# ProPrj_LXBRC-STM32F405__2024-08-19.net
KiCad netlist of a schematic drawn in EasyEDA Pro
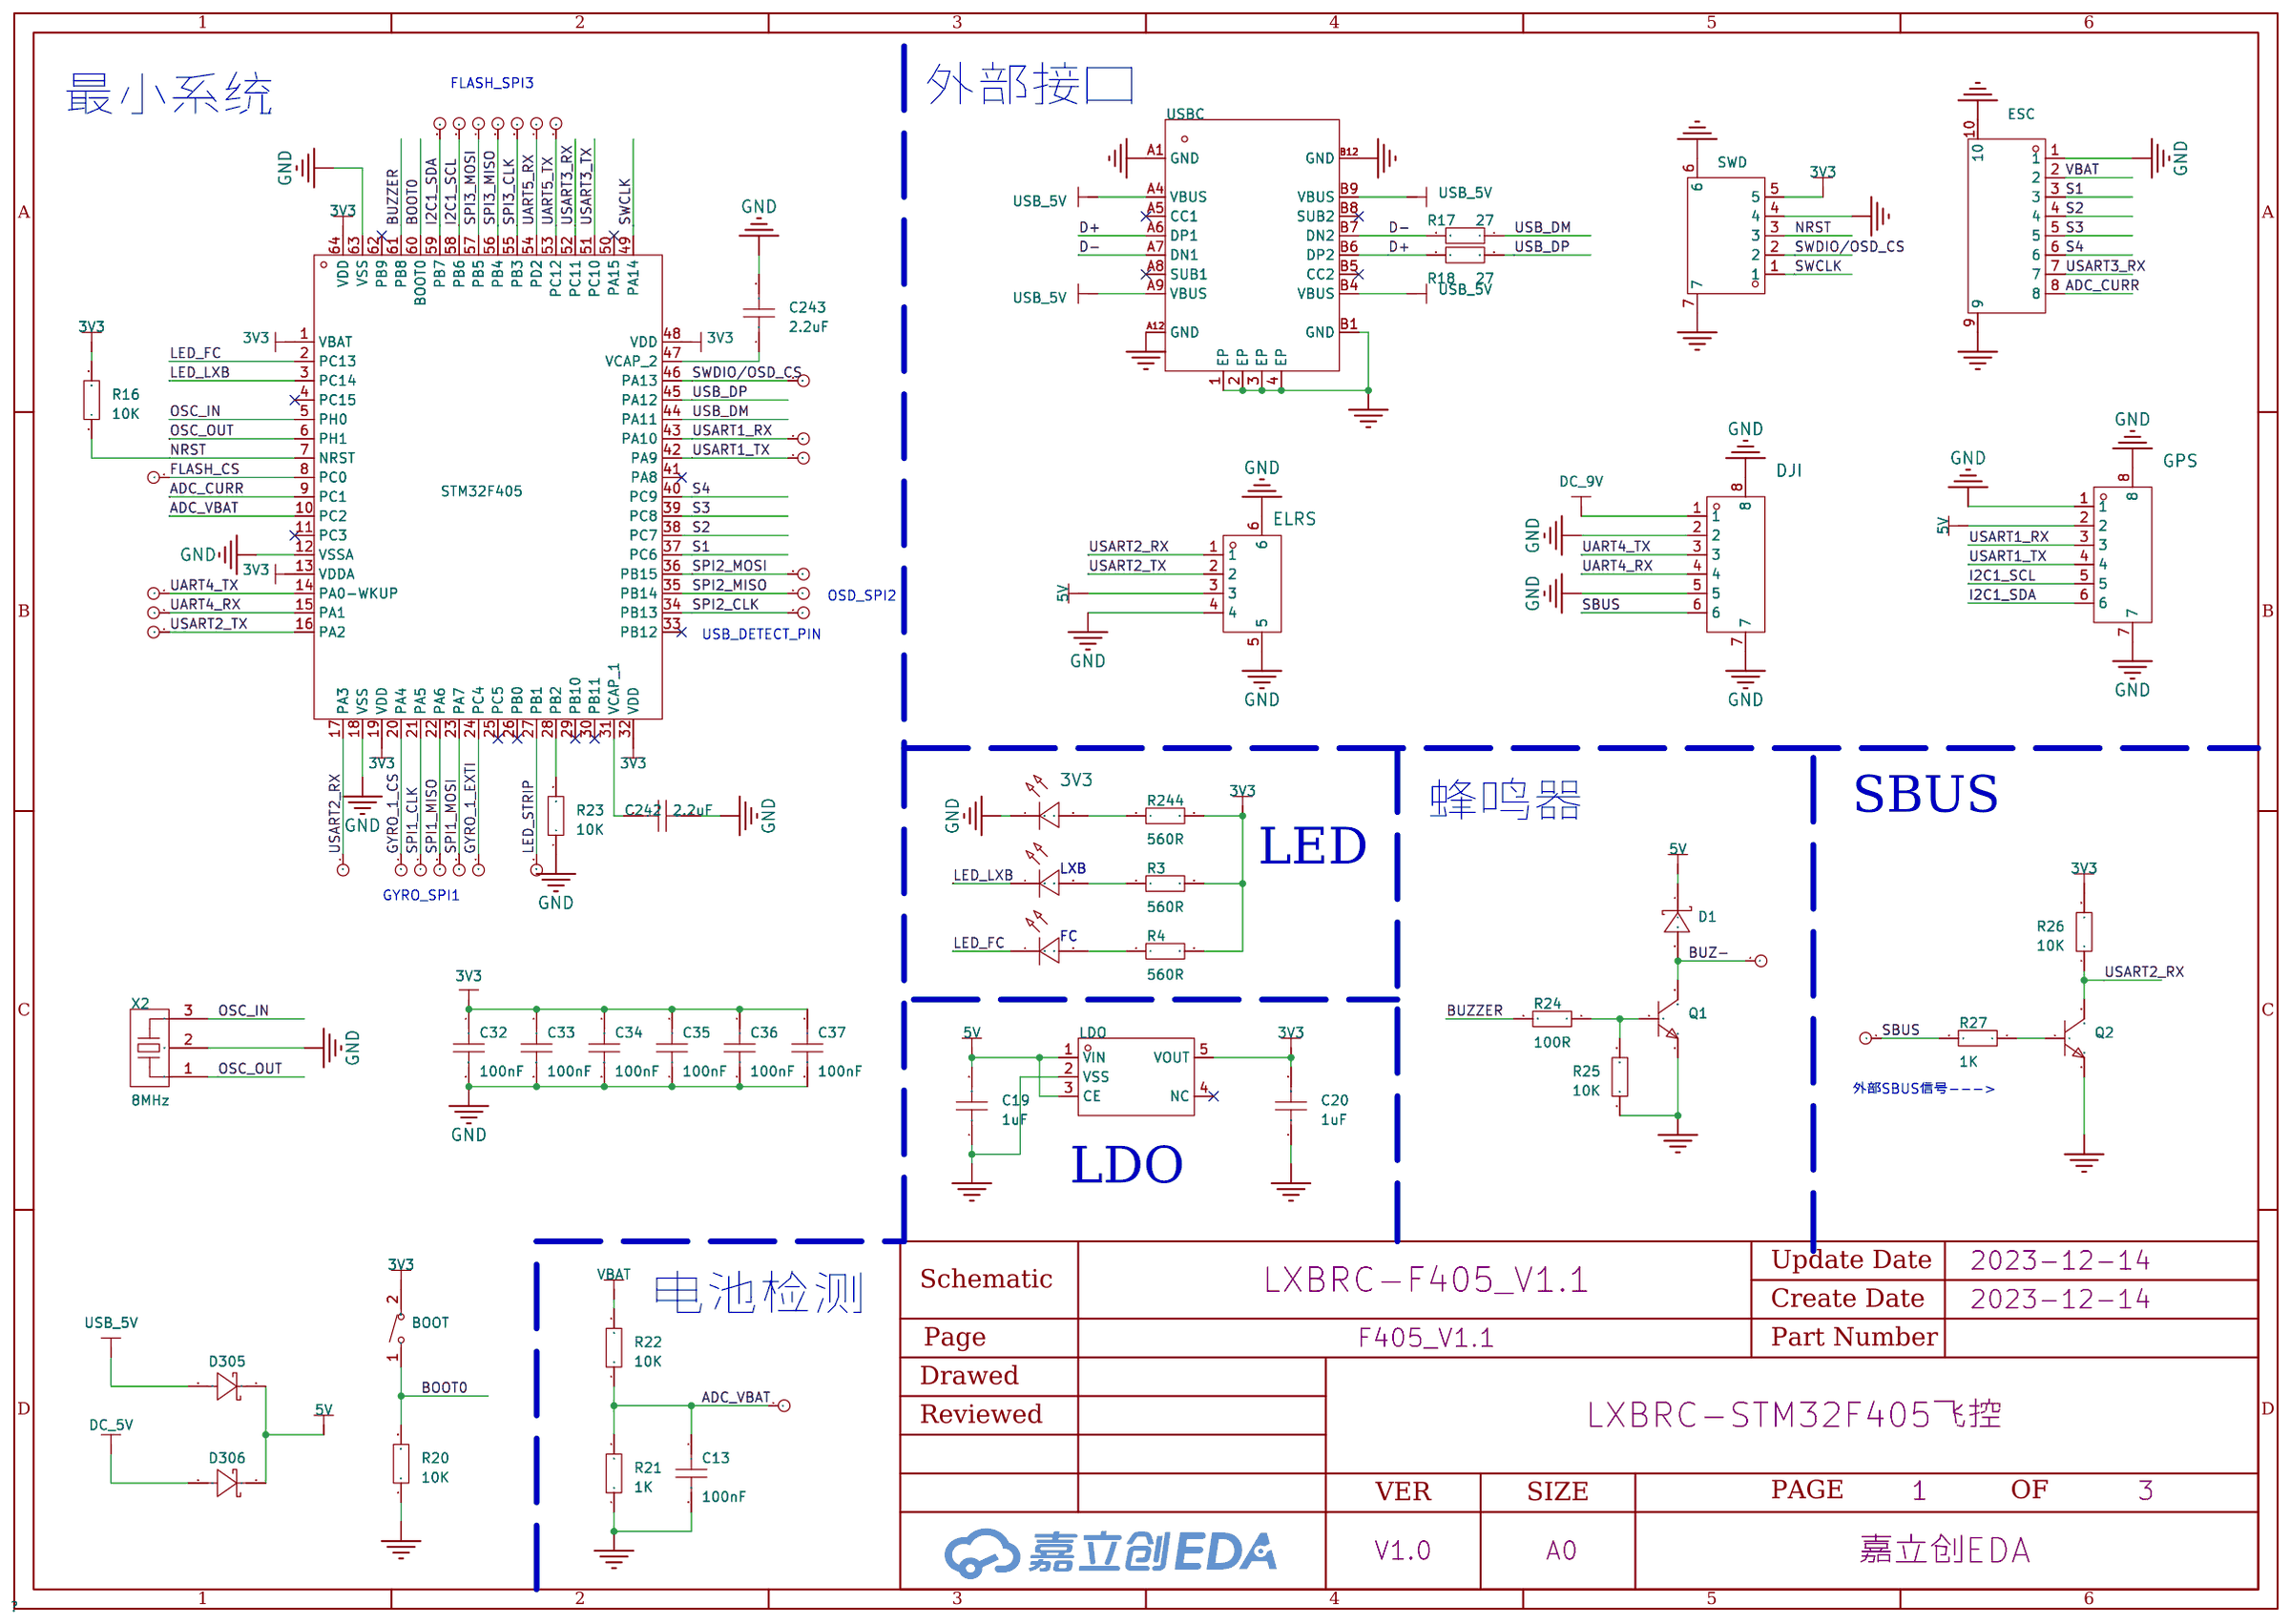
[diagram p0: F405_V1.1]
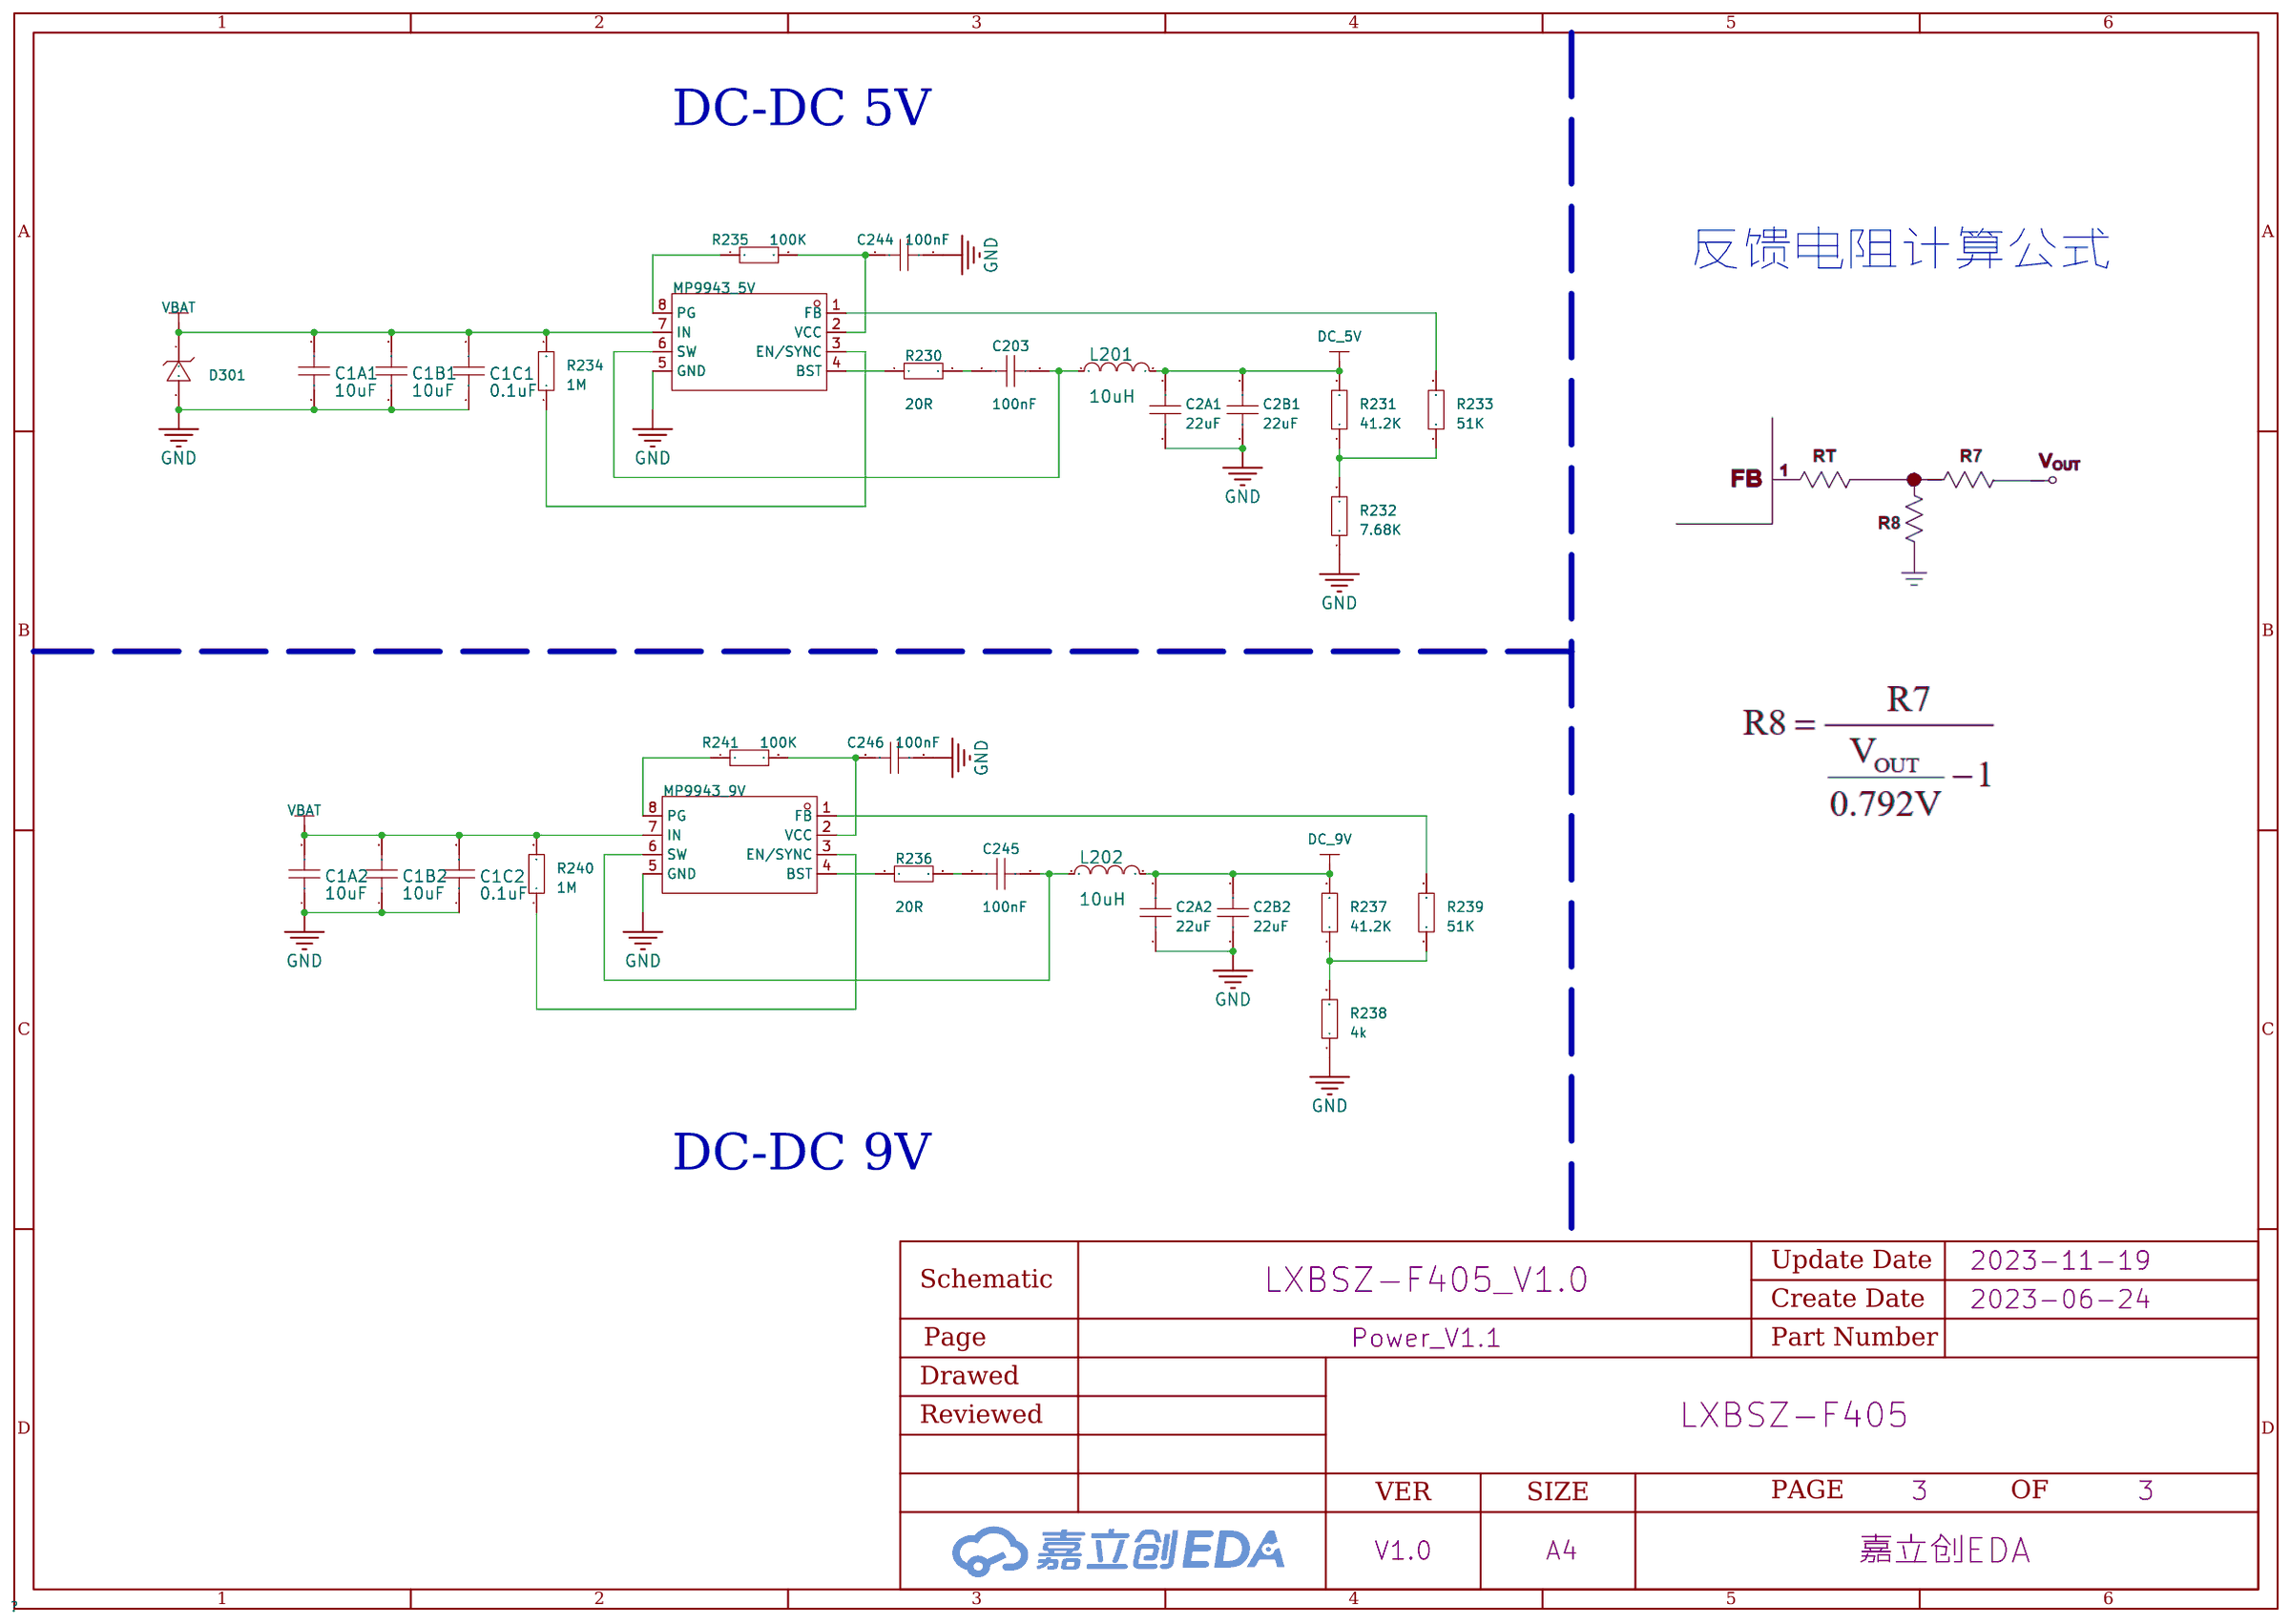
[diagram p1: Power_V1.1]
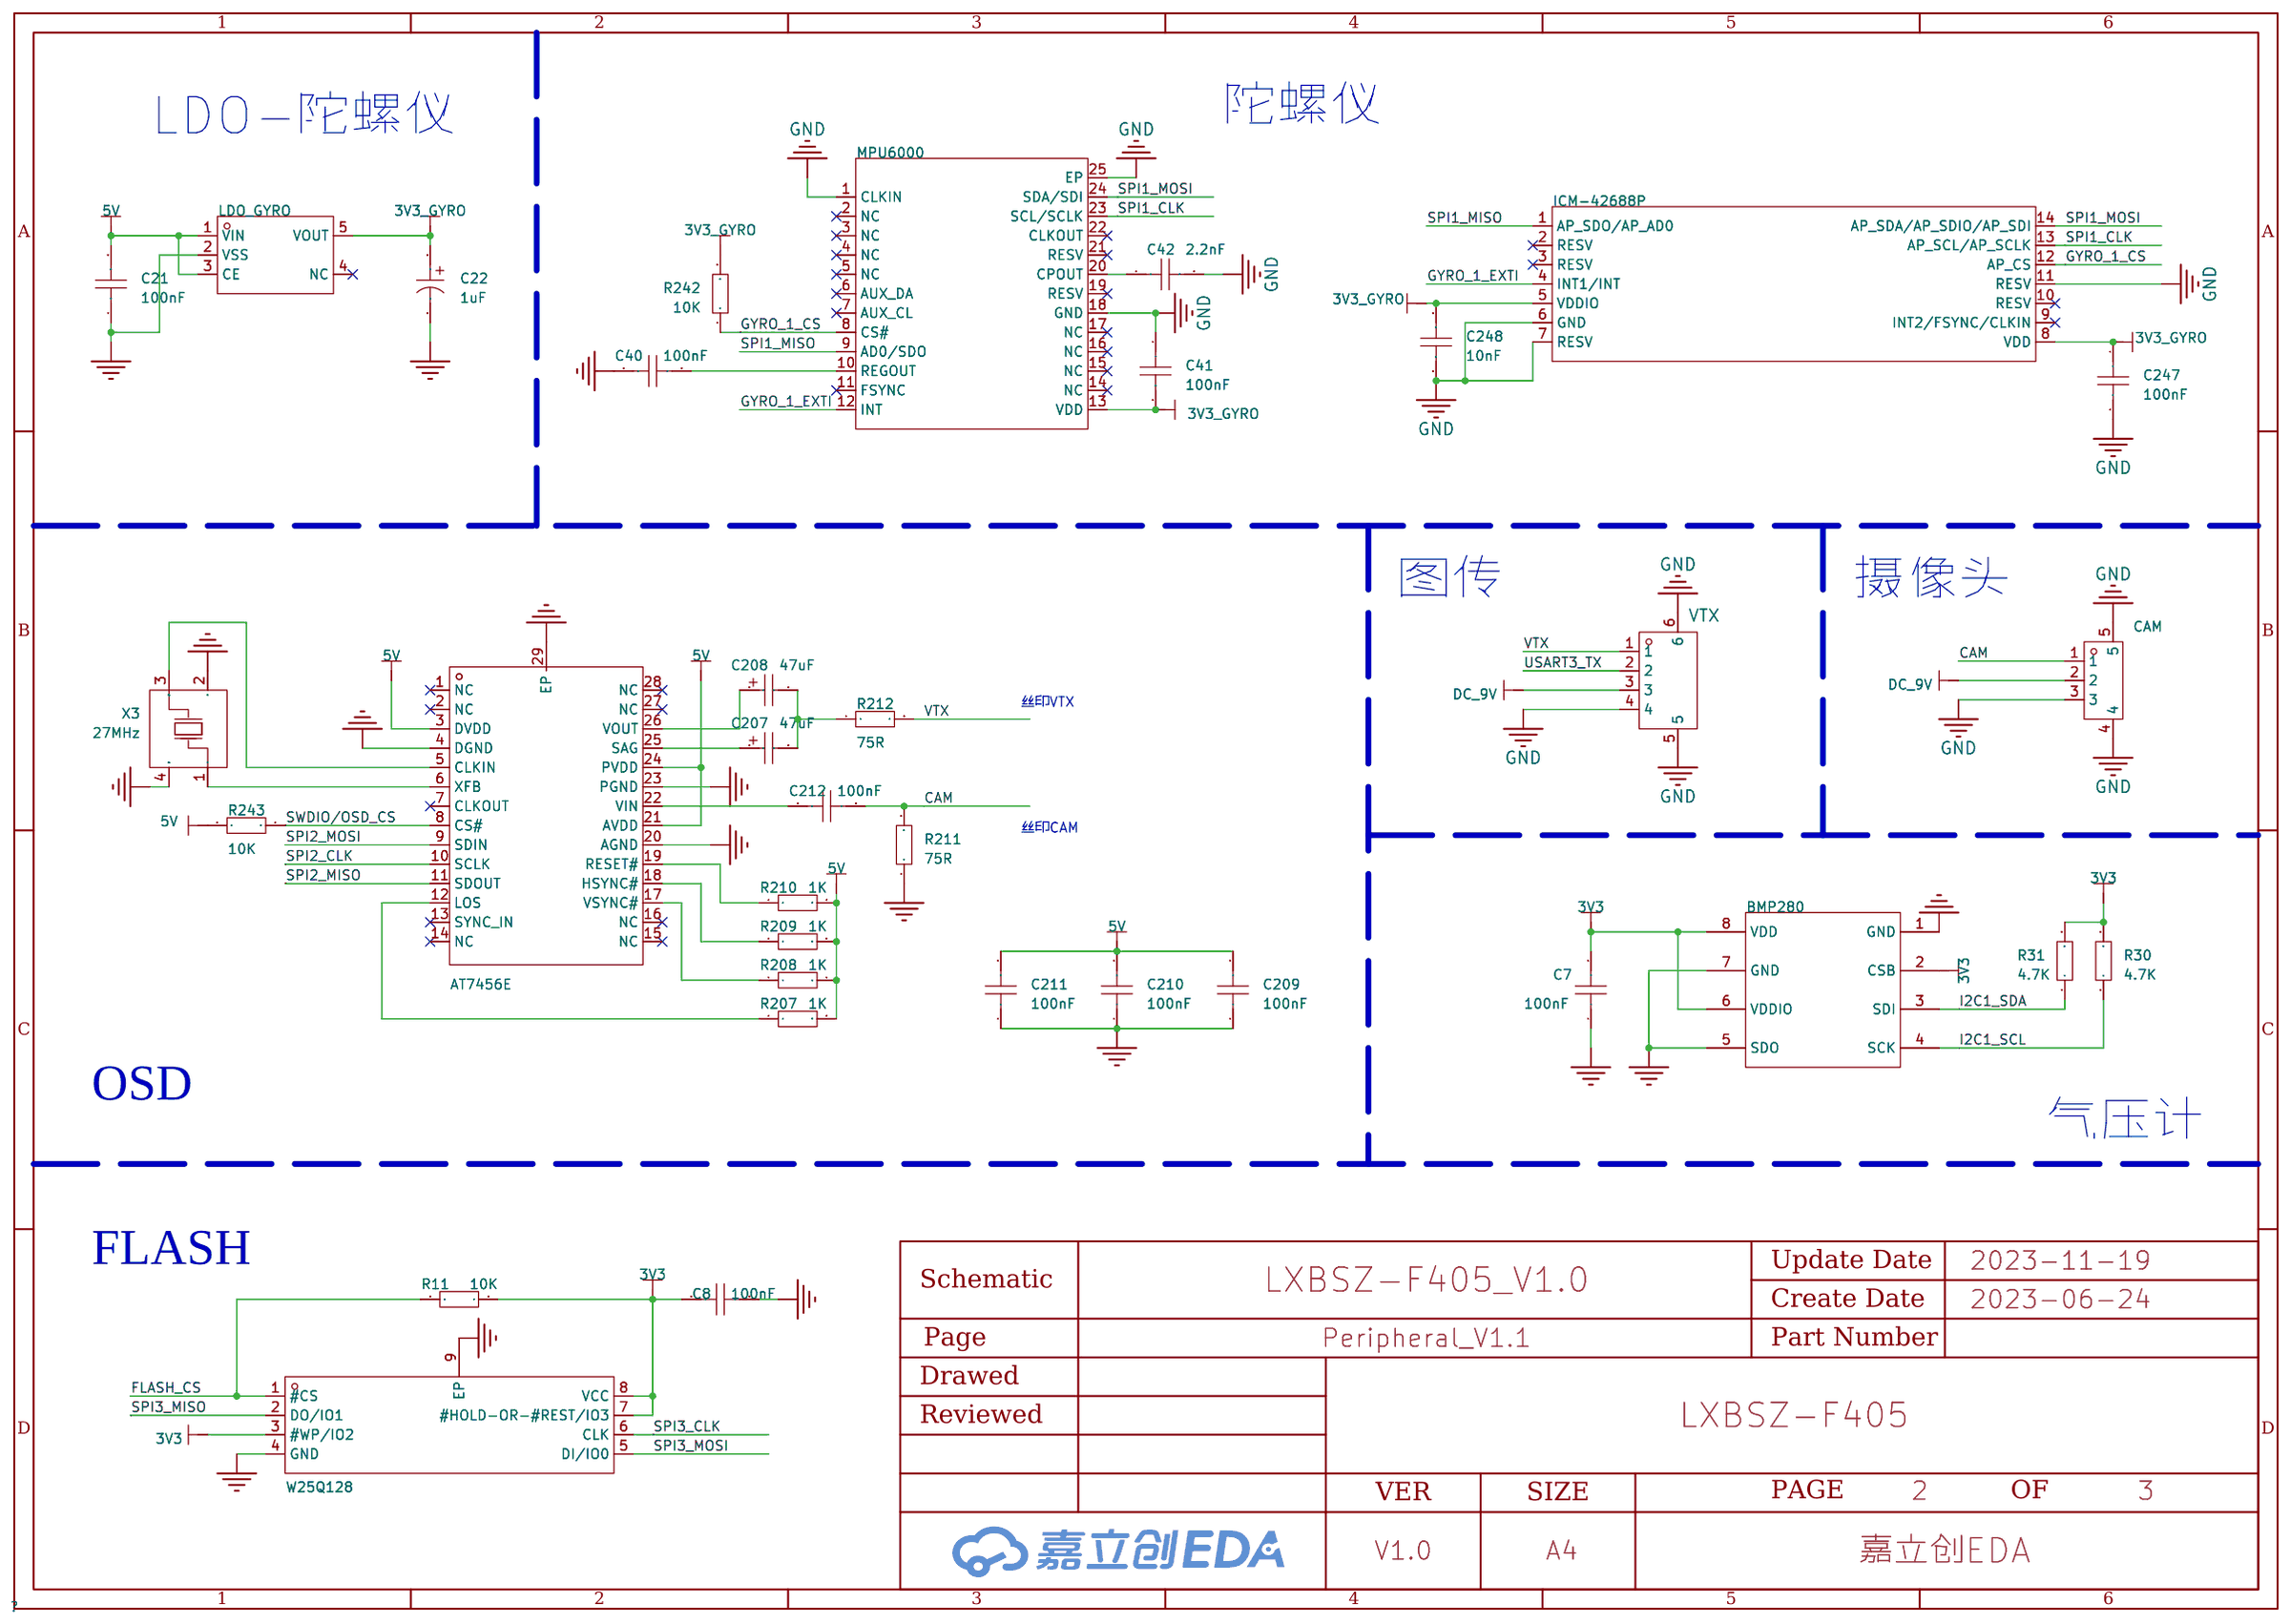
[diagram p2: Peripheral_V1.1]

(export (version "E")
  (design (tool "Eeschema 10.0.6"))
  (components
    (comp (ref "3V3")
      (value "~")
      (footprint "easyedapro:LED_0402")
      (libsource (lib "easyedapro") (part "LED_R"))
    )
    (comp (ref "BOOT")
      (value "TS2306A 200gf 002")
      (footprint "easyedapro:SW-SMD_L3.0-W2.0-LS3.5")
      (fields (field (name "Manufacturer") "SHOU HAN(首韩)"))
      (libsource (lib "easyedapro") (part "TS2306A 200GF 002"))
    )
    (comp (ref "C13")
      (value "100nF")
      (footprint "easyedapro:C0402")
      (libsource (lib "easyedapro") (part "CapAcitance"))
    )
    (comp (ref "C19")
      (value "1uF")
      (footprint "easyedapro:C0402")
      (libsource (lib "easyedapro") (part "CapAcitance"))
    )
    (comp (ref "C20")
      (value "1uF")
      (footprint "easyedapro:C0402")
      (libsource (lib "easyedapro") (part "CapAcitance"))
    )
    (comp (ref "C32")
      (value "100nF")
      (footprint "easyedapro:C0402")
      (libsource (lib "easyedapro") (part "CapAcitance"))
    )
    (comp (ref "C33")
      (value "100nF")
      (footprint "easyedapro:C0402")
      (libsource (lib "easyedapro") (part "CapAcitance"))
    )
    (comp (ref "C34")
      (value "100nF")
      (footprint "easyedapro:C0402")
      (libsource (lib "easyedapro") (part "CapAcitance"))
    )
    (comp (ref "C35")
      (value "100nF")
      (footprint "easyedapro:C0402")
      (libsource (lib "easyedapro") (part "CapAcitance"))
    )
    (comp (ref "C36")
      (value "100nF")
      (footprint "easyedapro:C0402")
      (libsource (lib "easyedapro") (part "CapAcitance"))
    )
    (comp (ref "C37")
      (value "100nF")
      (footprint "easyedapro:C0402")
      (libsource (lib "easyedapro") (part "CapAcitance"))
    )
    (comp (ref "C242")
      (value "2.2uF")
      (footprint "easyedapro:C0402")
      (libsource (lib "easyedapro") (part "CapAcitance"))
    )
    (comp (ref "C243")
      (value "2.2uF")
      (footprint "easyedapro:C0402")
      (libsource (lib "easyedapro") (part "CapAcitance"))
    )
    (comp (ref "D1")
      (value "B5819WS")
      (footprint "easyedapro:SOD-323_L1.8-W1.3-LS2.5-RD")
      (description "直流反向耐压(Vr):40V;平均整流电流(Io):1A;正向压降(Vf):900mV@3A;")
      (fields (field (name "Manufacturer") "Slkor(萨科微)"))
      (libsource (lib "easyedapro") (part "B5819WS_C488405"))
    )
    (comp (ref "D305")
      (value "B5819W")
      (footprint "easyedapro:SOD-123F_L2.7-W1.6-LS3.8-RD-1")
      (description "二极管配置:-;直流反向耐压(Vr):40V;平均整流电流(Io):1A;正向压降(Vf):580mV@1A;")
      (fields (field (name "Manufacturer") "GOODWORK(固得沃克)"))
      (libsource (lib "easyedapro") (part "B5819W_C2943878"))
    )
    (comp (ref "D306")
      (value "B5819W")
      (footprint "easyedapro:SOD-123F_L2.7-W1.6-LS3.8-RD-1")
      (description "二极管配置:-;直流反向耐压(Vr):40V;平均整流电流(Io):1A;正向压降(Vf):580mV@1A;")
      (fields (field (name "Manufacturer") "GOODWORK(固得沃克)"))
      (libsource (lib "easyedapro") (part "B5819W_C2943878"))
    )
    (comp (ref "DJI")
      (value "ZX-SH1.0-6PWT")
      (footprint "easyedapro:CONN-SMD_6P-P1.00_MEGASTAR_ZX-SH1.0-6PWT")
      (fields (field (name "Manufacturer") "Megastar(兆星)"))
      (libsource (lib "easyedapro") (part "ZX-SH1.0-6PWT"))
    )
    (comp (ref "ELRS")
      (value "ZX-SH1.0-4PWT")
      (footprint "easyedapro:CONN-SMD_4P-P1.00_MEGASTAR_ZX-SH1.0-4PWT")
      (fields (field (name "Manufacturer") "Megastar(兆星)"))
      (libsource (lib "easyedapro") (part "ZX-SH1.0-4PWT"))
    )
    (comp (ref "ESC")
      (value "A1002WR-S-8P")
      (footprint "easyedapro:CONN-SMD_A1002WR-S-8P")
      (description "系列:SH;连接器类型:接头;触头类型:公形引脚;间距:0.039quot;(1.00mm);针脚数:8;")
      (fields (field (name "Manufacturer") "CJT(长江连接器)"))
      (libsource (lib "easyedapro") (part "A1002WR-S-8P"))
    )
    (comp (ref "FC")
      (value "~")
      (footprint "easyedapro:LED_0402")
      (libsource (lib "easyedapro") (part "LED_B"))
    )
    (comp (ref "G2") (value "~") (footprint "easyedapro:通孔焊盘") (libsource (lib "easyedapro") (part "焊盘")))
    (comp (ref "G3") (value "~") (footprint "easyedapro:通孔焊盘") (libsource (lib "easyedapro") (part "焊盘")))
    (comp (ref "G4") (value "~") (footprint "easyedapro:通孔焊盘") (libsource (lib "easyedapro") (part "焊盘")))
    (comp (ref "G7") (value "~") (footprint "easyedapro:通孔焊盘") (libsource (lib "easyedapro") (part "焊盘")))
    (comp (ref "G8") (value "~") (footprint "easyedapro:通孔焊盘") (libsource (lib "easyedapro") (part "焊盘")))
    (comp (ref "G9") (value "~") (footprint "easyedapro:通孔焊盘") (libsource (lib "easyedapro") (part "焊盘")))
    (comp (ref "G10") (value "~") (footprint "easyedapro:通孔焊盘") (libsource (lib "easyedapro") (part "焊盘")))
    (comp (ref "G11") (value "~") (footprint "easyedapro:通孔焊盘") (libsource (lib "easyedapro") (part "焊盘")))
    (comp (ref "G12") (value "~") (footprint "easyedapro:通孔焊盘") (libsource (lib "easyedapro") (part "焊盘")))
    (comp (ref "G13") (value "~") (footprint "easyedapro:通孔焊盘") (libsource (lib "easyedapro") (part "焊盘")))
    (comp (ref "G14") (value "~") (footprint "easyedapro:通孔焊盘") (libsource (lib "easyedapro") (part "焊盘")))
    (comp (ref "G15") (value "~") (footprint "easyedapro:通孔焊盘") (libsource (lib "easyedapro") (part "焊盘")))
    (comp (ref "G16") (value "~") (footprint "easyedapro:通孔焊盘") (libsource (lib "easyedapro") (part "焊盘")))
    (comp (ref "G17") (value "~") (footprint "easyedapro:通孔焊盘") (libsource (lib "easyedapro") (part "焊盘")))
    (comp (ref "G18") (value "~") (footprint "easyedapro:通孔焊盘") (libsource (lib "easyedapro") (part "焊盘")))
    (comp (ref "G19") (value "~") (footprint "easyedapro:通孔焊盘") (libsource (lib "easyedapro") (part "焊盘")))
    (comp (ref "G20") (value "~") (footprint "easyedapro:通孔焊盘") (libsource (lib "easyedapro") (part "焊盘")))
    (comp (ref "G21") (value "~") (footprint "easyedapro:通孔焊盘") (libsource (lib "easyedapro") (part "焊盘")))
    (comp (ref "G22") (value "~") (footprint "easyedapro:通孔焊盘") (libsource (lib "easyedapro") (part "焊盘")))
    (comp (ref "G23") (value "~") (footprint "easyedapro:通孔焊盘") (libsource (lib "easyedapro") (part "焊盘")))
    (comp (ref "G24") (value "~") (footprint "easyedapro:通孔焊盘") (libsource (lib "easyedapro") (part "焊盘")))
    (comp (ref "G25") (value "~") (footprint "easyedapro:通孔焊盘") (libsource (lib "easyedapro") (part "焊盘")))
    (comp (ref "G26") (value "~") (footprint "easyedapro:通孔焊盘") (libsource (lib "easyedapro") (part "焊盘")))
    (comp (ref "G27") (value "~") (footprint "easyedapro:通孔焊盘") (libsource (lib "easyedapro") (part "焊盘")))
    (comp (ref "G28") (value "~") (footprint "easyedapro:通孔焊盘") (libsource (lib "easyedapro") (part "焊盘")))
    (comp (ref "GPS")
      (value "ZX-SH1.0-6PWT")
      (footprint "easyedapro:CONN-SMD_6P-P1.00_MEGASTAR_ZX-SH1.0-6PWT")
      (fields (field (name "Manufacturer") "Megastar(兆星)"))
      (libsource (lib "easyedapro") (part "ZX-SH1.0-6PWT"))
    )
    (comp (ref "HP15") (value "~") (footprint "easyedapro:通孔焊盘") (libsource (lib "easyedapro") (part "焊盘")))
    (comp (ref "LDO")
      (value "CJ6206B33M")
      (footprint "easyedapro:SOT-23-5_L2.9-W1.6-P0.95-LS2.8-BL")
      (fields (field (name "Manufacturer") "CJ(江苏长电/长晶)"))
      (libsource (lib "easyedapro") (part "CJ6206B33M"))
    )
    (comp (ref "LXB")
      (value "~")
      (footprint "easyedapro:LED_0402")
      (libsource (lib "easyedapro") (part "LED_G"))
    )
    (comp (ref "Q1")
      (value "~")
      (footprint "easyedapro:S8050_SOT-23")
      (libsource (lib "easyedapro") (part "NPN"))
    )
    (comp (ref "Q2")
      (value "~")
      (footprint "easyedapro:S8050_SOT-23")
      (libsource (lib "easyedapro") (part "NPN"))
    )
    (comp (ref "R3") (value "560R") (footprint "easyedapro:R0402") (libsource (lib "easyedapro") (part "电阻")))
    (comp (ref "R4") (value "560R") (footprint "easyedapro:R0402") (libsource (lib "easyedapro") (part "电阻")))
    (comp (ref "R16") (value "10K") (footprint "easyedapro:R0402") (libsource (lib "easyedapro") (part "电阻")))
    (comp (ref "R17") (value "27") (footprint "easyedapro:R0402") (libsource (lib "easyedapro") (part "电阻")))
    (comp (ref "R18") (value "27") (footprint "easyedapro:R0402") (libsource (lib "easyedapro") (part "电阻")))
    (comp (ref "R20") (value "10K") (footprint "easyedapro:R0402") (libsource (lib "easyedapro") (part "电阻")))
    (comp (ref "R21") (value "1K") (footprint "easyedapro:R0402") (libsource (lib "easyedapro") (part "电阻")))
    (comp (ref "R22") (value "10K") (footprint "easyedapro:R0402") (libsource (lib "easyedapro") (part "电阻")))
    (comp (ref "R23") (value "10K") (footprint "easyedapro:R0402") (libsource (lib "easyedapro") (part "电阻")))
    (comp (ref "R24")
      (value "100R")
      (footprint "easyedapro:R0402")
      (libsource (lib "easyedapro") (part "电阻"))
    )
    (comp (ref "R25") (value "10K") (footprint "easyedapro:R0402") (libsource (lib "easyedapro") (part "电阻")))
    (comp (ref "R26") (value "10K") (footprint "easyedapro:R0402") (libsource (lib "easyedapro") (part "电阻")))
    (comp (ref "R27") (value "1K") (footprint "easyedapro:R0402") (libsource (lib "easyedapro") (part "电阻")))
    (comp (ref "R244")
      (value "560R")
      (footprint "easyedapro:R0402")
      (libsource (lib "easyedapro") (part "电阻"))
    )
    (comp (ref "RC1") (value "~") (footprint "easyedapro:通孔焊盘") (libsource (lib "easyedapro") (part "焊盘")))
    (comp (ref "STM32F405")
      (value "STM32F405RGT6V")
      (footprint "easyedapro:LQFP-64_L10.0-W10.0-P0.50-LS12.0-BL")
      (fields (field (name "Manufacturer") "ST(意法半导体)"))
      (libsource (lib "easyedapro") (part "STM32F405RGT6V"))
    )
    (comp (ref "SWD")
      (value "A1002WR-S-5P")
      (footprint "easyedapro:CONN-SMD_A1002WR-S-5P")
      (description "系列:SH;连接器类型:接头;触头类型:公形引脚;间距:0.039quot;(1.00mm);针脚数:5;")
      (fields (field (name "Manufacturer") "CJT(长江连接器)"))
      (libsource (lib "easyedapro") (part "A1002WR-S-5P"))
    )
    (comp (ref "USBC")
      (value "KH-TYPE-C-16P")
      (footprint "easyedapro:USB-C-SMD_KH-TYPE-C-16P")
      (description "连接器类型:Type-C;标准:-;公母:母座;触点数量:16;端口数量:1;安装方式:卧贴;额定电流 - 电源:3A;工作温度范围:-40°C~+85°C;")
      (fields (field (name "Manufacturer") "kinghelm(金航标)"))
      (libsource (lib "easyedapro") (part "KH-TYPE-C-16P"))
    )
    (comp (ref "X2")
      (value "8MHz")
      (footprint "easyedapro:OSC-SMD_3P-L3.2-W1.3-P1.2-L")
      (description "频率:8MHz;频率容差:±0.1%;内置负载电容:33pF;谐振阻抗:40Ω;")
      (fields
        (field (name "Manufacturer Part") "CSTCE8M00G15C99-R0")
        (field (name "Manufacturer") "muRata(村田)")
      )
      (libsource (lib "easyedapro") (part "CSTCE8M00G15C99-R0"))
    )
    (comp (ref "C1A1") (value "10uF") (libsource (lib "easyedapro") (part "47uF")))
    (comp (ref "C1A2") (value "10uF") (libsource (lib "easyedapro") (part "47uF")))
    (comp (ref "C1B1") (value "10uF") (libsource (lib "easyedapro") (part "47uF")))
    (comp (ref "C1B2") (value "10uF") (libsource (lib "easyedapro") (part "47uF")))
    (comp (ref "C1C1") (value "0.1uF") (libsource (lib "easyedapro") (part "0.1uF")))
    (comp (ref "C1C2") (value "0.1uF") (libsource (lib "easyedapro") (part "0.1uF")))
    (comp (ref "C2A1")
      (value "22uF")
      (footprint "easyedapro:C0402")
      (libsource (lib "easyedapro") (part "CapAcitance"))
    )
    (comp (ref "C2A2")
      (value "22uF")
      (footprint "easyedapro:C0402")
      (libsource (lib "easyedapro") (part "CapAcitance"))
    )
    (comp (ref "C2B1")
      (value "22uF")
      (footprint "easyedapro:C0402")
      (libsource (lib "easyedapro") (part "CapAcitance"))
    )
    (comp (ref "C2B2")
      (value "22uF")
      (footprint "easyedapro:C0402")
      (libsource (lib "easyedapro") (part "CapAcitance"))
    )
    (comp (ref "C203")
      (value "100nF")
      (footprint "easyedapro:C0402")
      (libsource (lib "easyedapro") (part "CapAcitance"))
    )
    (comp (ref "C244")
      (value "100nF")
      (footprint "easyedapro:C0402")
      (libsource (lib "easyedapro") (part "CapAcitance"))
    )
    (comp (ref "C245")
      (value "100nF")
      (footprint "easyedapro:C0402")
      (libsource (lib "easyedapro") (part "CapAcitance"))
    )
    (comp (ref "C246")
      (value "100nF")
      (footprint "easyedapro:C0402")
      (libsource (lib "easyedapro") (part "CapAcitance"))
    )
    (comp (ref "D301")
      (value "SMF33A")
      (footprint "easyedapro:SOD-123FL_L2.7-W1.8-LS3.8-RD")
      (description "极性:单向;")
      (fields (field (name "Manufacturer") "TWGMC(台湾迪嘉)"))
      (libsource (lib "easyedapro") (part "SMF33A_C726914"))
    )
    (comp (ref "L201")
      (value "10uH")
      (footprint "easyedapro:IND-SMD_L4.4-W4.2")
      (description "类型:一体成型电感;电感值:10uH;精度:±20%;额定电流:1.6A;饱和电流(Isat):2.2A;")
      (fields (field (name "Manufacturer Part") "FXL0420-100-M") (field (name "Manufacturer") "cjiang(长江微电)"))
      (libsource (lib "easyedapro") (part "FXL0420-100-M"))
    )
    (comp (ref "L202")
      (value "10uH")
      (footprint "easyedapro:IND-SMD_L4.4-W4.2")
      (description "类型:一体成型电感;电感值:10uH;精度:±20%;额定电流:1.6A;饱和电流(Isat):2.2A;")
      (fields (field (name "Manufacturer Part") "FXL0420-100-M") (field (name "Manufacturer") "cjiang(长江微电)"))
      (libsource (lib "easyedapro") (part "FXL0420-100-M"))
    )
    (comp (ref "MP9943_5V")
      (value "MP9943GQ-Z")
      (footprint "easyedapro:QFN-8_L3.0-W3.0-P0.65-BL")
      (libsource (lib "easyedapro") (part "MP9943GQ-Z"))
    )
    (comp (ref "MP9943_9V")
      (value "MP9943GQ-Z")
      (footprint "easyedapro:QFN-8_L3.0-W3.0-P0.65-BL")
      (libsource (lib "easyedapro") (part "MP9943GQ-Z"))
    )
    (comp (ref "R230")
      (value "20R")
      (footprint "easyedapro:R0402")
      (libsource (lib "easyedapro") (part "电阻"))
    )
    (comp (ref "R231")
      (value "41.2K")
      (footprint "easyedapro:R0402")
      (libsource (lib "easyedapro") (part "电阻"))
    )
    (comp (ref "R232")
      (value "7.68K")
      (footprint "easyedapro:R0402")
      (libsource (lib "easyedapro") (part "电阻"))
    )
    (comp (ref "R233")
      (value "51K")
      (footprint "easyedapro:R0402")
      (libsource (lib "easyedapro") (part "电阻"))
    )
    (comp (ref "R234") (value "1M") (footprint "easyedapro:R0402") (libsource (lib "easyedapro") (part "电阻")))
    (comp (ref "R235")
      (value "100K")
      (footprint "easyedapro:R0402")
      (libsource (lib "easyedapro") (part "电阻"))
    )
    (comp (ref "R236")
      (value "20R")
      (footprint "easyedapro:R0402")
      (libsource (lib "easyedapro") (part "电阻"))
    )
    (comp (ref "R237")
      (value "41.2K")
      (footprint "easyedapro:R0402")
      (libsource (lib "easyedapro") (part "电阻"))
    )
    (comp (ref "R238") (value "4k") (footprint "easyedapro:R0402") (libsource (lib "easyedapro") (part "电阻")))
    (comp (ref "R239")
      (value "51K")
      (footprint "easyedapro:R0402")
      (libsource (lib "easyedapro") (part "电阻"))
    )
    (comp (ref "R240") (value "1M") (footprint "easyedapro:R0402") (libsource (lib "easyedapro") (part "电阻")))
    (comp (ref "R241")
      (value "100K")
      (footprint "easyedapro:R0402")
      (libsource (lib "easyedapro") (part "电阻"))
    )
    (comp (ref "AT7456E")
      (value "AT7456E")
      (footprint "easyedapro:TSSOP-28_L9.7-W4.4-P0.65-LS6.4-BL-EP-2")
      (description "视频字符叠加芯片，跟MAX7456-pin-pin")
      (fields (field (name "Manufacturer") "杭州中科微"))
      (libsource (lib "easyedapro") (part "AT7456E"))
    )
    (comp (ref "BMP280")
      (value "BMP280")
      (footprint "easyedapro:LGA-8_L2.5-W2.0-P0.65_AMP6127")
      (description "Bosch气压传感器新品，可测量大气压力，带高精度温度测量，可校准精确计算海拔高度。I2C或SPI接口，宽量程（300-1100hpa），精度高")
      (fields (field (name "Manufacturer") "Bosch(博世)"))
      (libsource (lib "easyedapro") (part "BMP280"))
    )
    (comp (ref "C7")
      (value "100nF")
      (footprint "easyedapro:C0402")
      (libsource (lib "easyedapro") (part "CapAcitance"))
    )
    (comp (ref "C8")
      (value "100nF")
      (footprint "easyedapro:C0402")
      (libsource (lib "easyedapro") (part "CapAcitance"))
    )
    (comp (ref "C21")
      (value "100nF")
      (footprint "easyedapro:C0402")
      (libsource (lib "easyedapro") (part "CapAcitance"))
    )
    (comp (ref "C22")
      (value "1uF")
      (footprint "easyedapro:CAP-SMD_L1.6-W0.8-RD")
      (description "容值:47uF;精度:±20%;额定电压:6.3V;漏电流:-;纹波电流:20mA@100kHz;等效串联电阻:10Ω@100kHz;工作温度:-55°C~+125°C;")
      (fields (field (name "Manufacturer Part") "F980J476MMA") (field (name "Manufacturer") "Kyocera AVX"))
      (libsource (lib "easyedapro") (part "F980J476MMA"))
    )
    (comp (ref "C40")
      (value "100nF")
      (footprint "easyedapro:C0402")
      (libsource (lib "easyedapro") (part "CapAcitance"))
    )
    (comp (ref "C41")
      (value "100nF")
      (footprint "easyedapro:C0402")
      (libsource (lib "easyedapro") (part "CapAcitance"))
    )
    (comp (ref "C42")
      (value "2.2nF")
      (footprint "easyedapro:C0402")
      (libsource (lib "easyedapro") (part "CapAcitance"))
    )
    (comp (ref "C207")
      (value "47uF")
      (footprint "easyedapro:CASE-A_3216")
      (description "容值:47uF;精度:±10%;额定电压:6.3V;等效串联电阻:1.6Ω@100kHz;")
      (fields (field (name "Manufacturer Part") "TAJA476K006RNJ") (field (name "Manufacturer") "Kyocera AVX"))
      (libsource (lib "easyedapro") (part "TAJA476K006RNJ"))
    )
    (comp (ref "C208")
      (value "47uF")
      (footprint "easyedapro:CASE-A_3216")
      (description "容值:47uF;精度:±10%;额定电压:6.3V;等效串联电阻:1.6Ω@100kHz;")
      (fields (field (name "Manufacturer Part") "TAJA476K006RNJ") (field (name "Manufacturer") "Kyocera AVX"))
      (libsource (lib "easyedapro") (part "TAJA476K006RNJ"))
    )
    (comp (ref "C209")
      (value "100nF")
      (footprint "easyedapro:C0402")
      (libsource (lib "easyedapro") (part "CapAcitance"))
    )
    (comp (ref "C210")
      (value "100nF")
      (footprint "easyedapro:C0402")
      (libsource (lib "easyedapro") (part "CapAcitance"))
    )
    (comp (ref "C211")
      (value "100nF")
      (footprint "easyedapro:C0402")
      (libsource (lib "easyedapro") (part "CapAcitance"))
    )
    (comp (ref "C212")
      (value "100nF")
      (footprint "easyedapro:C0402")
      (libsource (lib "easyedapro") (part "CapAcitance"))
    )
    (comp (ref "C247")
      (value "100nF")
      (footprint "easyedapro:C0402")
      (libsource (lib "easyedapro") (part "CapAcitance"))
    )
    (comp (ref "C248")
      (value "10nF")
      (footprint "easyedapro:C0402")
      (libsource (lib "easyedapro") (part "CapAcitance"))
    )
    (comp (ref "CAM")
      (value "WTB01W03BB")
      (footprint "easyedapro:CONN-SMD_3P-P1.00_BZCN_WTB01W03BB")
      (fields (field (name "Manufacturer") "BZCN(博众电气)"))
      (libsource (lib "easyedapro") (part "WTB01W03BB"))
    )
    (comp (ref "ICM-42688P")
      (value "ICM-42688-P")
      (footprint "easyedapro:LGA-14_L3.0-W2.5-P0.50-TL")
      (fields (field (name "Manufacturer") "TDK InvenSense(应美盛)"))
      (libsource (lib "easyedapro") (part "ICM-42688-P"))
    )
    (comp (ref "LDO_GYRO")
      (value "CJ6206B33M")
      (footprint "easyedapro:SOT-23-5_L2.9-W1.6-P0.95-LS2.8-BL")
      (fields (field (name "Manufacturer") "CJ(江苏长电/长晶)"))
      (libsource (lib "easyedapro") (part "CJ6206B33M"))
    )
    (comp (ref "MPU6000")
      (value "MPU-6000")
      (footprint "easyedapro:QFN-24_L4.0-W4.0-P0.50-BL-EP2.7")
      (description "三轴加速度计和三轴陀螺仪")
      (fields (field (name "Manufacturer") "TDK InvenSense(应美盛)"))
      (libsource (lib "easyedapro") (part "MPU-6000"))
    )
    (comp (ref "R11") (value "10K") (footprint "easyedapro:R0402") (libsource (lib "easyedapro") (part "电阻")))
    (comp (ref "R30")
      (value "4.7K")
      (footprint "easyedapro:R0402")
      (libsource (lib "easyedapro") (part "电阻"))
    )
    (comp (ref "R31")
      (value "4.7K")
      (footprint "easyedapro:R0402")
      (libsource (lib "easyedapro") (part "电阻"))
    )
    (comp (ref "R207") (value "1K") (footprint "easyedapro:R0402") (libsource (lib "easyedapro") (part "电阻")))
    (comp (ref "R208") (value "1K") (footprint "easyedapro:R0402") (libsource (lib "easyedapro") (part "电阻")))
    (comp (ref "R209") (value "1K") (footprint "easyedapro:R0402") (libsource (lib "easyedapro") (part "电阻")))
    (comp (ref "R210") (value "1K") (footprint "easyedapro:R0402") (libsource (lib "easyedapro") (part "电阻")))
    (comp (ref "R211")
      (value "75R")
      (footprint "easyedapro:R0402")
      (libsource (lib "easyedapro") (part "电阻"))
    )
    (comp (ref "R212")
      (value "75R")
      (footprint "easyedapro:R0402")
      (libsource (lib "easyedapro") (part "电阻"))
    )
    (comp (ref "R242")
      (value "10K")
      (footprint "easyedapro:R0402")
      (libsource (lib "easyedapro") (part "电阻"))
    )
    (comp (ref "R243")
      (value "10K")
      (footprint "easyedapro:R0402")
      (libsource (lib "easyedapro") (part "电阻"))
    )
    (comp (ref "VTX")
      (value "ZX-SH1.0-4PWT")
      (footprint "easyedapro:CONN-SMD_4P-P1.00_MEGASTAR_ZX-SH1.0-4PWT")
      (fields (field (name "Manufacturer") "Megastar(兆星)"))
      (libsource (lib "easyedapro") (part "ZX-SH1.0-4PWT"))
    )
    (comp (ref "W25Q128")
      (value "W25Q128JVPIQ")
      (footprint "easyedapro:WSON-8_L6.0-W5.0-P1.27-BL-EP")
      (fields (field (name "Manufacturer") "WINBOND(华邦)"))
      (libsource (lib "easyedapro") (part "W25Q128JVPIQTR"))
    )
    (comp (ref "X3")
      (value "27MHz")
      (footprint "easyedapro:OSC-SMD_4P-L3.2-W2.5-BL")
      (description "频率:27MHz;频率公差:±10ppm;负载电容:20pF;")
      (fields (field (name "Manufacturer Part") "X322527MSB4SI") (field (name "Manufacturer") "YXC(扬兴晶振)"))
      (libsource (lib "easyedapro") (part "X322527MSB4SI"))
    )
  )
  (nets
    (net (code "1") (name "3V3") (class "Default")
      (node (ref "BMP280") (pin "2") (pinfunction "CSB_2") (pintype "input"))
      (node (ref "BMP280") (pin "6") (pinfunction "VDDIO_6") (pintype "input"))
      (node (ref "BMP280") (pin "8") (pinfunction "VDD_8") (pintype "input"))
      (node (ref "BOOT") (pin "2") (pinfunction "A&apos;_2") (pintype "input"))
      (node (ref "C20") (pin "2") (pinfunction "2_2") (pintype "input"))
      (node (ref "C32") (pin "1") (pinfunction "1_1") (pintype "input"))
      (node (ref "C33") (pin "1") (pinfunction "1_1") (pintype "input"))
      (node (ref "C34") (pin "1") (pinfunction "1_1") (pintype "input"))
      (node (ref "C35") (pin "1") (pinfunction "1_1") (pintype "input"))
      (node (ref "C36") (pin "1") (pinfunction "1_1") (pintype "input"))
      (node (ref "C37") (pin "1") (pinfunction "1_1") (pintype "input"))
      (node (ref "C7") (pin "2") (pinfunction "2_2") (pintype "input"))
      (node (ref "C8") (pin "2") (pinfunction "2_2") (pintype "input"))
      (node (ref "LDO") (pin "5") (pinfunction "VOUT_5") (pintype "input"))
      (node (ref "R11") (pin "2") (pinfunction "2_2") (pintype "input"))
      (node (ref "R16") (pin "2") (pinfunction "2_2") (pintype "input"))
      (node (ref "R244") (pin "2") (pinfunction "2_2") (pintype "input"))
      (node (ref "R26") (pin "2") (pinfunction "2_2") (pintype "input"))
      (node (ref "R3") (pin "2") (pinfunction "2_2") (pintype "input"))
      (node (ref "R30") (pin "2") (pinfunction "2_2") (pintype "input"))
      (node (ref "R31") (pin "2") (pinfunction "2_2") (pintype "input"))
      (node (ref "R4") (pin "2") (pinfunction "2_2") (pintype "input"))
      (node (ref "STM32F405") (pin "1") (pinfunction "VBAT_1") (pintype "input"))
      (node (ref "STM32F405") (pin "13") (pinfunction "VDDA_13") (pintype "input"))
      (node (ref "STM32F405") (pin "19") (pinfunction "VDD_19") (pintype "input"))
      (node (ref "STM32F405") (pin "32") (pinfunction "VDD_32") (pintype "input"))
      (node (ref "STM32F405") (pin "48") (pinfunction "VDD_48") (pintype "input"))
      (node (ref "STM32F405") (pin "64") (pinfunction "VDD_64") (pintype "input"))
      (node (ref "SWD") (pin "5") (pinfunction "5_5") (pintype "input"))
      (node (ref "W25Q128") (pin "3") (pinfunction "#WP/IO2_3") (pintype "input"))
      (node (ref "W25Q128") (pin "7") (pinfunction "#HOLD-OR-#REST/IO3_7") (pintype "input"))
      (node (ref "W25Q128") (pin "8") (pinfunction "VCC_8") (pintype "input"))
    )
    (net (code "2") (name "3V3_GYRO") (class "Default")
      (node (ref "C22") (pin "1") (pinfunction "1_1") (pintype "input"))
      (node (ref "C247") (pin "1") (pinfunction "1_1") (pintype "input"))
      (node (ref "C248") (pin "1") (pinfunction "1_1") (pintype "input"))
      (node (ref "C41") (pin "2") (pinfunction "2_2") (pintype "input"))
      (node (ref "ICM-42688P") (pin "5") (pinfunction "VDDIO_5") (pintype "input"))
      (node (ref "ICM-42688P") (pin "8") (pinfunction "VDD_8") (pintype "input"))
      (node (ref "LDO_GYRO") (pin "5") (pinfunction "VOUT_5") (pintype "input"))
      (node (ref "MPU6000") (pin "13") (pinfunction "VDD_13") (pintype "input"))
      (node (ref "R242") (pin "2") (pinfunction "2_2") (pintype "input"))
    )
    (net (code "3") (name "5V") (class "Default")
      (node (ref "AT7456E") (pin "21") (pinfunction "AVDD_21") (pintype "input"))
      (node (ref "AT7456E") (pin "24") (pinfunction "PVDD_24") (pintype "input"))
      (node (ref "AT7456E") (pin "3") (pinfunction "DVDD_3") (pintype "input"))
      (node (ref "C19") (pin "2") (pinfunction "2_2") (pintype "input"))
      (node (ref "C209") (pin "2") (pinfunction "2_2") (pintype "input"))
      (node (ref "C21") (pin "2") (pinfunction "2_2") (pintype "input"))
      (node (ref "C210") (pin "2") (pinfunction "2_2") (pintype "input"))
      (node (ref "C211") (pin "2") (pinfunction "2_2") (pintype "input"))
      (node (ref "D1") (pin "1") (pinfunction "K_1") (pintype "input"))
      (node (ref "D305") (pin "1") (pinfunction "K_1") (pintype "input"))
      (node (ref "D306") (pin "1") (pinfunction "K_1") (pintype "input"))
      (node (ref "ELRS") (pin "3") (pinfunction "3_3") (pintype "input"))
      (node (ref "GPS") (pin "2") (pinfunction "2_2") (pintype "input"))
      (node (ref "LDO") (pin "1") (pinfunction "VIN_1") (pintype "input"))
      (node (ref "LDO") (pin "3") (pinfunction "CE_3") (pintype "input"))
      (node (ref "LDO_GYRO") (pin "1") (pinfunction "VIN_1") (pintype "input"))
      (node (ref "LDO_GYRO") (pin "3") (pinfunction "CE_3") (pintype "input"))
      (node (ref "R207") (pin "2") (pinfunction "2_2") (pintype "input"))
      (node (ref "R208") (pin "2") (pinfunction "2_2") (pintype "input"))
      (node (ref "R209") (pin "2") (pinfunction "2_2") (pintype "input"))
      (node (ref "R210") (pin "2") (pinfunction "2_2") (pintype "input"))
      (node (ref "R243") (pin "2") (pinfunction "2_2") (pintype "input"))
    )
    (net (code "4") (name "ADC_CURR") (class "Default")
      (node (ref "ESC") (pin "8") (pinfunction "8_8") (pintype "input"))
      (node (ref "STM32F405") (pin "9") (pinfunction "PC1_9") (pintype "input"))
    )
    (net (code "5") (name "ADC_VBAT") (class "Default")
      (node (ref "C13") (pin "1") (pinfunction "1_1") (pintype "input"))
      (node (ref "HP15") (pin "1") (pinfunction "1_1") (pintype "input"))
      (node (ref "R21") (pin "2") (pinfunction "2_2") (pintype "input"))
      (node (ref "R22") (pin "1") (pinfunction "1_1") (pintype "input"))
      (node (ref "STM32F405") (pin "10") (pinfunction "PC2_10") (pintype "input"))
    )
    (net (code "6") (name "BOOT0") (class "Default")
      (node (ref "BOOT") (pin "1") (pinfunction "A_1") (pintype "input"))
      (node (ref "R20") (pin "2") (pinfunction "2_2") (pintype "input"))
      (node (ref "STM32F405") (pin "60") (pinfunction "BOOT0_60") (pintype "input"))
    )
    (net (code "7") (name "BUZ-") (class "Default")
      (node (ref "D1") (pin "2") (pinfunction "A_2") (pintype "input"))
      (node (ref "G28") (pin "1") (pinfunction "1_1") (pintype "input"))
      (node (ref "Q1") (pin "3") (pinfunction "3_3") (pintype "unspecified"))
    )
    (net (code "8") (name "BUZZER") (class "Default")
      (node (ref "R24") (pin "2") (pinfunction "2_2") (pintype "input"))
      (node (ref "STM32F405") (pin "61") (pinfunction "PB8_61") (pintype "input"))
    )
    (net (code "9") (name "CAM") (class "Default")
      (node (ref "C212") (pin "2") (pinfunction "2_2") (pintype "input"))
      (node (ref "CAM") (pin "1") (pinfunction "1_1") (pintype "input"))
      (node (ref "R211") (pin "2") (pinfunction "2_2") (pintype "input"))
    )
    (net (code "10") (name "D+") (class "Default")
      (node (ref "R18") (pin "2") (pinfunction "2_2") (pintype "input"))
      (node (ref "USBC") (pin "A6") (pinfunction "DP1_A6") (pintype "input"))
      (node (ref "USBC") (pin "B6") (pinfunction "DP2_B6") (pintype "input"))
    )
    (net (code "11") (name "D-") (class "Default")
      (node (ref "R17") (pin "2") (pinfunction "2_2") (pintype "input"))
      (node (ref "USBC") (pin "A7") (pinfunction "DN1_A7") (pintype "input"))
      (node (ref "USBC") (pin "B7") (pinfunction "DN2_B7") (pintype "input"))
    )
    (net (code "12") (name "DC_5V") (class "Default")
      (node (ref "C2A1") (pin "2") (pinfunction "2_2") (pintype "input"))
      (node (ref "C2B1") (pin "2") (pinfunction "2_2") (pintype "input"))
      (node (ref "D306") (pin "2") (pinfunction "A_2") (pintype "input"))
      (node (ref "L201") (pin "2") (pinfunction "2_2") (pintype "input"))
      (node (ref "R231") (pin "2") (pinfunction "2_2") (pintype "input"))
    )
    (net (code "13") (name "DC_9V") (class "Default")
      (node (ref "C2A2") (pin "2") (pinfunction "2_2") (pintype "input"))
      (node (ref "C2B2") (pin "2") (pinfunction "2_2") (pintype "input"))
      (node (ref "CAM") (pin "2") (pinfunction "2_2") (pintype "input"))
      (node (ref "DJI") (pin "1") (pinfunction "1_1") (pintype "input"))
      (node (ref "L202") (pin "2") (pinfunction "2_2") (pintype "input"))
      (node (ref "R237") (pin "2") (pinfunction "2_2") (pintype "input"))
      (node (ref "VTX") (pin "3") (pinfunction "3_3") (pintype "input"))
    )
    (net (code "14") (name "FLASH_CS") (class "Default")
      (node (ref "G12") (pin "1") (pinfunction "1_1") (pintype "input"))
      (node (ref "R11") (pin "1") (pinfunction "1_1") (pintype "input"))
      (node (ref "STM32F405") (pin "8") (pinfunction "PC0_8") (pintype "input"))
      (node (ref "W25Q128") (pin "1") (pinfunction "#CS_1") (pintype "input"))
    )
    (net (code "15") (name "GND") (class "Default")
      (node (ref "3V3") (pin "1") (pinfunction "C_1") (pintype "input"))
      (node (ref "AT7456E") (pin "20") (pinfunction "AGND_20") (pintype "input"))
      (node (ref "AT7456E") (pin "23") (pinfunction "PGND_23") (pintype "input"))
      (node (ref "AT7456E") (pin "29") (pinfunction "EP_29") (pintype "input"))
      (node (ref "AT7456E") (pin "4") (pinfunction "DGND_4") (pintype "input"))
      (node (ref "BMP280") (pin "1") (pinfunction "GND_1") (pintype "input"))
      (node (ref "BMP280") (pin "5") (pinfunction "SDO_5") (pintype "input"))
      (node (ref "BMP280") (pin "7") (pinfunction "GND_7") (pintype "input"))
      (node (ref "C13") (pin "2") (pinfunction "2_2") (pintype "input"))
      (node (ref "C19") (pin "1") (pinfunction "1_1") (pintype "input"))
      (node (ref "C1A1") (pin "1") (pinfunction "1_1") (pintype "input"))
      (node (ref "C1A2") (pin "1") (pinfunction "1_1") (pintype "input"))
      (node (ref "C1B1") (pin "1") (pinfunction "1_1") (pintype "input"))
      (node (ref "C1B2") (pin "1") (pinfunction "1_1") (pintype "input"))
      (node (ref "C1C1") (pin "1") (pinfunction "1_1") (pintype "input"))
      (node (ref "C1C2") (pin "1") (pinfunction "1_1") (pintype "input"))
      (node (ref "C20") (pin "1") (pinfunction "1_1") (pintype "input"))
      (node (ref "C209") (pin "1") (pinfunction "1_1") (pintype "input"))
      (node (ref "C21") (pin "1") (pinfunction "1_1") (pintype "input"))
      (node (ref "C210") (pin "1") (pinfunction "1_1") (pintype "input"))
      (node (ref "C211") (pin "1") (pinfunction "1_1") (pintype "input"))
      (node (ref "C22") (pin "2") (pinfunction "2_2") (pintype "input"))
      (node (ref "C242") (pin "2") (pinfunction "2_2") (pintype "input"))
      (node (ref "C243") (pin "2") (pinfunction "2_2") (pintype "input"))
      (node (ref "C244") (pin "1") (pinfunction "1_1") (pintype "input"))
      (node (ref "C246") (pin "1") (pinfunction "1_1") (pintype "input"))
      (node (ref "C247") (pin "2") (pinfunction "2_2") (pintype "input"))
      (node (ref "C248") (pin "2") (pinfunction "2_2") (pintype "input"))
      (node (ref "C2A1") (pin "1") (pinfunction "1_1") (pintype "input"))
      (node (ref "C2A2") (pin "1") (pinfunction "1_1") (pintype "input"))
      (node (ref "C2B1") (pin "1") (pinfunction "1_1") (pintype "input"))
      (node (ref "C2B2") (pin "1") (pinfunction "1_1") (pintype "input"))
      (node (ref "C32") (pin "2") (pinfunction "2_2") (pintype "input"))
      (node (ref "C33") (pin "2") (pinfunction "2_2") (pintype "input"))
      (node (ref "C34") (pin "2") (pinfunction "2_2") (pintype "input"))
      (node (ref "C35") (pin "2") (pinfunction "2_2") (pintype "input"))
      (node (ref "C36") (pin "2") (pinfunction "2_2") (pintype "input"))
      (node (ref "C37") (pin "2") (pinfunction "2_2") (pintype "input"))
      (node (ref "C40") (pin "2") (pinfunction "2_2") (pintype "input"))
      (node (ref "C41") (pin "1") (pinfunction "1_1") (pintype "input"))
      (node (ref "C42") (pin "2") (pinfunction "2_2") (pintype "input"))
      (node (ref "C7") (pin "1") (pinfunction "1_1") (pintype "input"))
      (node (ref "C8") (pin "1") (pinfunction "1_1") (pintype "input"))
      (node (ref "CAM") (pin "3") (pinfunction "3_3") (pintype "input"))
      (node (ref "CAM") (pin "4") (pinfunction "4_4") (pintype "input"))
      (node (ref "CAM") (pin "5") (pinfunction "5_5") (pintype "input"))
      (node (ref "D301") (pin "2") (pinfunction "2_2") (pintype "input"))
      (node (ref "DJI") (pin "2") (pinfunction "2_2") (pintype "input"))
      (node (ref "DJI") (pin "5") (pinfunction "5_5") (pintype "input"))
      (node (ref "DJI") (pin "7") (pinfunction "7_7") (pintype "input"))
      (node (ref "DJI") (pin "8") (pinfunction "8_8") (pintype "input"))
      (node (ref "ELRS") (pin "4") (pinfunction "4_4") (pintype "input"))
      (node (ref "ELRS") (pin "5") (pinfunction "5_5") (pintype "input"))
      (node (ref "ELRS") (pin "6") (pinfunction "6_6") (pintype "input"))
      (node (ref "ESC") (pin "1") (pinfunction "1_1") (pintype "input"))
      (node (ref "ESC") (pin "10") (pinfunction "10_10") (pintype "input"))
      (node (ref "ESC") (pin "9") (pinfunction "9_9") (pintype "input"))
      (node (ref "GPS") (pin "1") (pinfunction "1_1") (pintype "input"))
      (node (ref "GPS") (pin "7") (pinfunction "7_7") (pintype "input"))
      (node (ref "GPS") (pin "8") (pinfunction "8_8") (pintype "input"))
      (node (ref "ICM-42688P") (pin "11") (pinfunction "RESV_11") (pintype "input"))
      (node (ref "ICM-42688P") (pin "6") (pinfunction "GND_6") (pintype "input"))
      (node (ref "ICM-42688P") (pin "7") (pinfunction "RESV_7") (pintype "input"))
      (node (ref "LDO") (pin "2") (pinfunction "VSS_2") (pintype "input"))
      (node (ref "LDO_GYRO") (pin "2") (pinfunction "VSS_2") (pintype "input"))
      (node (ref "MP9943_5V") (pin "5") (pinfunction "GND_5") (pintype "input"))
      (node (ref "MP9943_9V") (pin "5") (pinfunction "GND_5") (pintype "input"))
      (node (ref "MPU6000") (pin "1") (pinfunction "CLKIN_1") (pintype "input"))
      (node (ref "MPU6000") (pin "18") (pinfunction "GND_18") (pintype "input"))
      (node (ref "MPU6000") (pin "25") (pinfunction "EP_25") (pintype "input"))
      (node (ref "Q1") (pin "2") (pinfunction "2_2") (pintype "unspecified"))
      (node (ref "Q2") (pin "2") (pinfunction "2_2") (pintype "unspecified"))
      (node (ref "R20") (pin "1") (pinfunction "1_1") (pintype "input"))
      (node (ref "R21") (pin "1") (pinfunction "1_1") (pintype "input"))
      (node (ref "R211") (pin "1") (pinfunction "1_1") (pintype "input"))
      (node (ref "R23") (pin "1") (pinfunction "1_1") (pintype "input"))
      (node (ref "R232") (pin "1") (pinfunction "1_1") (pintype "input"))
      (node (ref "R238") (pin "1") (pinfunction "1_1") (pintype "input"))
      (node (ref "R25") (pin "1") (pinfunction "1_1") (pintype "input"))
      (node (ref "STM32F405") (pin "12") (pinfunction "VSSA_12") (pintype "input"))
      (node (ref "STM32F405") (pin "18") (pinfunction "VSS_18") (pintype "input"))
      (node (ref "STM32F405") (pin "63") (pinfunction "VSS_63") (pintype "input"))
      (node (ref "SWD") (pin "4") (pinfunction "4_4") (pintype "input"))
      (node (ref "SWD") (pin "6") (pinfunction "6_6") (pintype "input"))
      (node (ref "SWD") (pin "7") (pinfunction "7_7") (pintype "input"))
      (node (ref "USBC") (pin "1") (pinfunction "EP_1") (pintype "input"))
      (node (ref "USBC") (pin "2") (pinfunction "EP_2") (pintype "input"))
      (node (ref "USBC") (pin "3") (pinfunction "EP_3") (pintype "input"))
      (node (ref "USBC") (pin "4") (pinfunction "EP_4") (pintype "input"))
      (node (ref "USBC") (pin "A1") (pinfunction "GND_A1") (pintype "input"))
      (node (ref "USBC") (pin "A12") (pinfunction "GND_A12") (pintype "input"))
      (node (ref "USBC") (pin "B1") (pinfunction "GND_B1") (pintype "input"))
      (node (ref "USBC") (pin "B12") (pinfunction "GND_B12") (pintype "input"))
      (node (ref "VTX") (pin "4") (pinfunction "4_4") (pintype "input"))
      (node (ref "VTX") (pin "5") (pinfunction "5_5") (pintype "input"))
      (node (ref "VTX") (pin "6") (pinfunction "6_6") (pintype "input"))
      (node (ref "W25Q128") (pin "4") (pinfunction "GND_4") (pintype "input"))
      (node (ref "W25Q128") (pin "9") (pinfunction "EP_9") (pintype "input"))
      (node (ref "X2") (pin "2") (pinfunction "2_2") (pintype "input"))
      (node (ref "X3") (pin "2") (pinfunction "GND_2") (pintype "input"))
      (node (ref "X3") (pin "4") (pinfunction "GND_4") (pintype "input"))
    )
    (net (code "16") (name "GYRO_1_CS") (class "Default")
      (node (ref "G16") (pin "1") (pinfunction "1_1") (pintype "input"))
      (node (ref "ICM-42688P") (pin "12") (pinfunction "AP_CS_12") (pintype "input"))
      (node (ref "MPU6000") (pin "8") (pinfunction "CS#_8") (pintype "input"))
      (node (ref "R242") (pin "1") (pinfunction "1_1") (pintype "input"))
      (node (ref "STM32F405") (pin "20") (pinfunction "PA4_20") (pintype "input"))
    )
    (net (code "17") (name "GYRO_1_EXTI") (class "Default")
      (node (ref "G20") (pin "1") (pinfunction "1_1") (pintype "input"))
      (node (ref "ICM-42688P") (pin "4") (pinfunction "INT1/INT_4") (pintype "input"))
      (node (ref "MPU6000") (pin "12") (pinfunction "INT_12") (pintype "input"))
      (node (ref "STM32F405") (pin "24") (pinfunction "PC4_24") (pintype "input"))
    )
    (net (code "18") (name "I2C1_SCL") (class "Default")
      (node (ref "BMP280") (pin "4") (pinfunction "SCK_4") (pintype "input"))
      (node (ref "G15") (pin "1") (pinfunction "1_1") (pintype "input"))
      (node (ref "GPS") (pin "5") (pinfunction "5_5") (pintype "input"))
      (node (ref "R30") (pin "1") (pinfunction "1_1") (pintype "input"))
      (node (ref "STM32F405") (pin "58") (pinfunction "PB6_58") (pintype "input"))
    )
    (net (code "19") (name "I2C1_SDA") (class "Default")
      (node (ref "BMP280") (pin "3") (pinfunction "SDI_3") (pintype "input"))
      (node (ref "G14") (pin "1") (pinfunction "1_1") (pintype "input"))
      (node (ref "GPS") (pin "6") (pinfunction "6_6") (pintype "input"))
      (node (ref "R31") (pin "1") (pinfunction "1_1") (pintype "input"))
      (node (ref "STM32F405") (pin "59") (pinfunction "PB7_59") (pintype "input"))
    )
    (net (code "20") (name "LED_FC") (class "Default")
      (node (ref "FC") (pin "1") (pinfunction "C_1") (pintype "input"))
      (node (ref "STM32F405") (pin "2") (pinfunction "PC13_2") (pintype "input"))
    )
    (net (code "21") (name "LED_LXB") (class "Default")
      (node (ref "LXB") (pin "1") (pinfunction "C_1") (pintype "input"))
      (node (ref "STM32F405") (pin "3") (pinfunction "PC14_3") (pintype "input"))
    )
    (net (code "22") (name "LED_STRIP") (class "Default")
      (node (ref "G27") (pin "1") (pinfunction "1_1") (pintype "input"))
      (node (ref "STM32F405") (pin "27") (pinfunction "PB1_27") (pintype "input"))
    )
    (net (code "23") (name "NRST") (class "Default")
      (node (ref "R16") (pin "1") (pinfunction "1_1") (pintype "input"))
      (node (ref "STM32F405") (pin "7") (pinfunction "NRST_7") (pintype "input"))
      (node (ref "SWD") (pin "3") (pinfunction "3_3") (pintype "input"))
    )
    (net (code "24") (name "Net-(3V3-A)") (class "Default")
      (node (ref "3V3") (pin "2") (pinfunction "A_2") (pintype "input"))
      (node (ref "R244") (pin "1") (pinfunction "1_1") (pintype "input"))
    )
    (net (code "25") (name "Net-(AT7456E-CLKIN)") (class "Default")
      (node (ref "AT7456E") (pin "5") (pinfunction "CLKIN_5") (pintype "input"))
      (node (ref "X3") (pin "3") (pinfunction "OSC2_3") (pintype "input"))
    )
    (net (code "26") (name "Net-(AT7456E-HSYNC#)") (class "Default")
      (node (ref "AT7456E") (pin "18") (pinfunction "HSYNC#_18") (pintype "input"))
      (node (ref "R209") (pin "1") (pinfunction "1_1") (pintype "input"))
    )
    (net (code "27") (name "Net-(AT7456E-LOS)") (class "Default")
      (node (ref "AT7456E") (pin "12") (pinfunction "LOS_12") (pintype "input"))
      (node (ref "R207") (pin "1") (pinfunction "1_1") (pintype "input"))
    )
    (net (code "28") (name "Net-(AT7456E-RESET#)") (class "Default")
      (node (ref "AT7456E") (pin "19") (pinfunction "RESET#_19") (pintype "input"))
      (node (ref "R210") (pin "1") (pinfunction "1_1") (pintype "input"))
    )
    (net (code "29") (name "Net-(AT7456E-SAG)") (class "Default")
      (node (ref "AT7456E") (pin "25") (pinfunction "SAG_25") (pintype "input"))
      (node (ref "C207") (pin "1") (pinfunction "1_1") (pintype "input"))
    )
    (net (code "30") (name "Net-(AT7456E-VIN)") (class "Default")
      (node (ref "AT7456E") (pin "22") (pinfunction "VIN_22") (pintype "input"))
      (node (ref "C212") (pin "1") (pinfunction "1_1") (pintype "input"))
    )
    (net (code "31") (name "Net-(AT7456E-VOUT)") (class "Default")
      (node (ref "AT7456E") (pin "26") (pinfunction "VOUT_26") (pintype "input"))
      (node (ref "C208") (pin "1") (pinfunction "1_1") (pintype "input"))
    )
    (net (code "32") (name "Net-(AT7456E-VSYNC#)") (class "Default")
      (node (ref "AT7456E") (pin "17") (pinfunction "VSYNC#_17") (pintype "input"))
      (node (ref "R208") (pin "1") (pinfunction "1_1") (pintype "input"))
    )
    (net (code "33") (name "Net-(AT7456E-XFB)") (class "Default")
      (node (ref "AT7456E") (pin "6") (pinfunction "XFB_6") (pintype "input"))
      (node (ref "X3") (pin "1") (pinfunction "OSC1_1") (pintype "input"))
    )
    (net (code "34") (name "Net-(C203-Pad1)") (class "Default")
      (node (ref "C203") (pin "1") (pinfunction "1_1") (pintype "input"))
      (node (ref "R230") (pin "2") (pinfunction "2_2") (pintype "input"))
    )
    (net (code "35") (name "Net-(C207-Pad2)") (class "Default")
      (node (ref "C207") (pin "2") (pinfunction "2_2") (pintype "input"))
      (node (ref "C208") (pin "2") (pinfunction "2_2") (pintype "input"))
      (node (ref "R212") (pin "1") (pinfunction "1_1") (pintype "input"))
    )
    (net (code "36") (name "Net-(C245-Pad1)") (class "Default")
      (node (ref "C245") (pin "1") (pinfunction "1_1") (pintype "input"))
      (node (ref "R236") (pin "2") (pinfunction "2_2") (pintype "input"))
    )
    (net (code "37") (name "Net-(FC-A)") (class "Default")
      (node (ref "FC") (pin "2") (pinfunction "A_2") (pintype "input"))
      (node (ref "R4") (pin "1") (pinfunction "1_1") (pintype "input"))
    )
    (net (code "38") (name "Net-(LXB-A)") (class "Default")
      (node (ref "LXB") (pin "2") (pinfunction "A_2") (pintype "input"))
      (node (ref "R3") (pin "1") (pinfunction "1_1") (pintype "input"))
    )
    (net (code "39") (name "Net-(MP9943_5V-BST)") (class "Default")
      (node (ref "MP9943_5V") (pin "4") (pinfunction "BST_4") (pintype "input"))
      (node (ref "R230") (pin "1") (pinfunction "1_1") (pintype "input"))
    )
    (net (code "40") (name "Net-(MP9943_5V-EN{slash}SYNC)") (class "Default")
      (node (ref "MP9943_5V") (pin "3") (pinfunction "EN/SYNC_3") (pintype "input"))
      (node (ref "R234") (pin "1") (pinfunction "1_1") (pintype "input"))
    )
    (net (code "41") (name "Net-(MP9943_5V-FB)") (class "Default")
      (node (ref "MP9943_5V") (pin "1") (pinfunction "FB_1") (pintype "input"))
      (node (ref "R233") (pin "2") (pinfunction "2_2") (pintype "input"))
    )
    (net (code "42") (name "Net-(MP9943_5V-PG)") (class "Default")
      (node (ref "MP9943_5V") (pin "8") (pinfunction "PG_8") (pintype "input"))
      (node (ref "R235") (pin "1") (pinfunction "1_1") (pintype "input"))
    )
    (net (code "43") (name "Net-(MP9943_5V-SW)") (class "Default")
      (node (ref "C203") (pin "2") (pinfunction "2_2") (pintype "input"))
      (node (ref "L201") (pin "1") (pinfunction "1_1") (pintype "input"))
      (node (ref "MP9943_5V") (pin "6") (pinfunction "SW_6") (pintype "input"))
    )
    (net (code "44") (name "Net-(MP9943_5V-VCC)") (class "Default")
      (node (ref "C244") (pin "2") (pinfunction "2_2") (pintype "input"))
      (node (ref "MP9943_5V") (pin "2") (pinfunction "VCC_2") (pintype "input"))
      (node (ref "R235") (pin "2") (pinfunction "2_2") (pintype "input"))
    )
    (net (code "45") (name "Net-(MP9943_9V-BST)") (class "Default")
      (node (ref "MP9943_9V") (pin "4") (pinfunction "BST_4") (pintype "input"))
      (node (ref "R236") (pin "1") (pinfunction "1_1") (pintype "input"))
    )
    (net (code "46") (name "Net-(MP9943_9V-EN{slash}SYNC)") (class "Default")
      (node (ref "MP9943_9V") (pin "3") (pinfunction "EN/SYNC_3") (pintype "input"))
      (node (ref "R240") (pin "1") (pinfunction "1_1") (pintype "input"))
    )
    (net (code "47") (name "Net-(MP9943_9V-FB)") (class "Default")
      (node (ref "MP9943_9V") (pin "1") (pinfunction "FB_1") (pintype "input"))
      (node (ref "R239") (pin "2") (pinfunction "2_2") (pintype "input"))
    )
    (net (code "48") (name "Net-(MP9943_9V-PG)") (class "Default")
      (node (ref "MP9943_9V") (pin "8") (pinfunction "PG_8") (pintype "input"))
      (node (ref "R241") (pin "1") (pinfunction "1_1") (pintype "input"))
    )
    (net (code "49") (name "Net-(MP9943_9V-SW)") (class "Default")
      (node (ref "C245") (pin "2") (pinfunction "2_2") (pintype "input"))
      (node (ref "L202") (pin "1") (pinfunction "1_1") (pintype "input"))
      (node (ref "MP9943_9V") (pin "6") (pinfunction "SW_6") (pintype "input"))
    )
    (net (code "50") (name "Net-(MP9943_9V-VCC)") (class "Default")
      (node (ref "C246") (pin "2") (pinfunction "2_2") (pintype "input"))
      (node (ref "MP9943_9V") (pin "2") (pinfunction "VCC_2") (pintype "input"))
      (node (ref "R241") (pin "2") (pinfunction "2_2") (pintype "input"))
    )
    (net (code "51") (name "Net-(MPU6000-CPOUT)") (class "Default")
      (node (ref "C42") (pin "1") (pinfunction "1_1") (pintype "input"))
      (node (ref "MPU6000") (pin "20") (pinfunction "CPOUT_20") (pintype "input"))
    )
    (net (code "52") (name "Net-(MPU6000-REGOUT)") (class "Default")
      (node (ref "C40") (pin "1") (pinfunction "1_1") (pintype "input"))
      (node (ref "MPU6000") (pin "10") (pinfunction "REGOUT_10") (pintype "input"))
    )
    (net (code "53") (name "Net-(Q1-Pad1)") (class "Default")
      (node (ref "Q1") (pin "1") (pinfunction "1_1") (pintype "unspecified"))
      (node (ref "R24") (pin "1") (pinfunction "1_1") (pintype "input"))
      (node (ref "R25") (pin "2") (pinfunction "2_2") (pintype "input"))
    )
    (net (code "54") (name "Net-(Q2-Pad1)") (class "Default")
      (node (ref "Q2") (pin "1") (pinfunction "1_1") (pintype "unspecified"))
      (node (ref "R27") (pin "1") (pinfunction "1_1") (pintype "input"))
    )
    (net (code "55") (name "Net-(R231-Pad1)") (class "Default")
      (node (ref "R231") (pin "1") (pinfunction "1_1") (pintype "input"))
      (node (ref "R232") (pin "2") (pinfunction "2_2") (pintype "input"))
      (node (ref "R233") (pin "1") (pinfunction "1_1") (pintype "input"))
    )
    (net (code "56") (name "Net-(R237-Pad1)") (class "Default")
      (node (ref "R237") (pin "1") (pinfunction "1_1") (pintype "input"))
      (node (ref "R238") (pin "2") (pinfunction "2_2") (pintype "input"))
      (node (ref "R239") (pin "1") (pinfunction "1_1") (pintype "input"))
    )
    (net (code "57") (name "Net-(STM32F405-PB2)") (class "Default")
      (node (ref "R23") (pin "2") (pinfunction "2_2") (pintype "input"))
      (node (ref "STM32F405") (pin "28") (pinfunction "PB2_28") (pintype "input"))
    )
    (net (code "58") (name "Net-(STM32F405-VCAP_1)") (class "Default")
      (node (ref "C242") (pin "1") (pinfunction "1_1") (pintype "input"))
      (node (ref "STM32F405") (pin "31") (pinfunction "VCAP_1_31") (pintype "input"))
    )
    (net (code "59") (name "Net-(STM32F405-VCAP_2)") (class "Default")
      (node (ref "C243") (pin "1") (pinfunction "1_1") (pintype "input"))
      (node (ref "STM32F405") (pin "47") (pinfunction "VCAP_2_47") (pintype "input"))
    )
    (net (code "60") (name "OSC_IN") (class "Default")
      (node (ref "STM32F405") (pin "5") (pinfunction "PH0_5") (pintype "input"))
      (node (ref "X2") (pin "3") (pinfunction "3_3") (pintype "input"))
    )
    (net (code "61") (name "OSC_OUT") (class "Default")
      (node (ref "STM32F405") (pin "6") (pinfunction "PH1_6") (pintype "input"))
      (node (ref "X2") (pin "1") (pinfunction "1_1") (pintype "input"))
    )
    (net (code "62") (name "S1") (class "Default")
      (node (ref "ESC") (pin "3") (pinfunction "3_3") (pintype "input"))
      (node (ref "STM32F405") (pin "37") (pinfunction "PC6_37") (pintype "input"))
    )
    (net (code "63") (name "S2") (class "Default")
      (node (ref "ESC") (pin "4") (pinfunction "4_4") (pintype "input"))
      (node (ref "STM32F405") (pin "38") (pinfunction "PC7_38") (pintype "input"))
    )
    (net (code "64") (name "S3") (class "Default")
      (node (ref "ESC") (pin "5") (pinfunction "5_5") (pintype "input"))
      (node (ref "STM32F405") (pin "39") (pinfunction "PC8_39") (pintype "input"))
    )
    (net (code "65") (name "S4") (class "Default")
      (node (ref "ESC") (pin "6") (pinfunction "6_6") (pintype "input"))
      (node (ref "STM32F405") (pin "40") (pinfunction "PC9_40") (pintype "input"))
    )
    (net (code "66") (name "SBUS") (class "Default")
      (node (ref "DJI") (pin "6") (pinfunction "6_6") (pintype "input"))
      (node (ref "R27") (pin "2") (pinfunction "2_2") (pintype "input"))
      (node (ref "RC1") (pin "1") (pinfunction "1_1") (pintype "input"))
    )
    (net (code "67") (name "SPI1_CLK") (class "Default")
      (node (ref "G17") (pin "1") (pinfunction "1_1") (pintype "input"))
      (node (ref "ICM-42688P") (pin "13") (pinfunction "AP_SCL/AP_SCLK_13") (pintype "input"))
      (node (ref "MPU6000") (pin "23") (pinfunction "SCL/SCLK_23") (pintype "input"))
      (node (ref "STM32F405") (pin "21") (pinfunction "PA5_21") (pintype "input"))
    )
    (net (code "68") (name "SPI1_MISO") (class "Default")
      (node (ref "G18") (pin "1") (pinfunction "1_1") (pintype "input"))
      (node (ref "ICM-42688P") (pin "1") (pinfunction "AP_SDO/AP_AD0_1") (pintype "input"))
      (node (ref "MPU6000") (pin "9") (pinfunction "AD0/SDO_9") (pintype "input"))
      (node (ref "STM32F405") (pin "22") (pinfunction "PA6_22") (pintype "input"))
    )
    (net (code "69") (name "SPI1_MOSI") (class "Default")
      (node (ref "G19") (pin "1") (pinfunction "1_1") (pintype "input"))
      (node (ref "ICM-42688P") (pin "14") (pinfunction "AP_SDA/AP_SDIO/AP_SDI_14") (pintype "input"))
      (node (ref "MPU6000") (pin "24") (pinfunction "SDA/SDI_24") (pintype "input"))
      (node (ref "STM32F405") (pin "23") (pinfunction "PA7_23") (pintype "input"))
    )
    (net (code "70") (name "SPI2_CLK") (class "Default")
      (node (ref "AT7456E") (pin "10") (pinfunction "SCLK_10") (pintype "input"))
      (node (ref "G23") (pin "1") (pinfunction "1_1") (pintype "input"))
      (node (ref "STM32F405") (pin "34") (pinfunction "PB13_34") (pintype "input"))
    )
    (net (code "71") (name "SPI2_MISO") (class "Default")
      (node (ref "AT7456E") (pin "11") (pinfunction "SDOUT_11") (pintype "input"))
      (node (ref "G22") (pin "1") (pinfunction "1_1") (pintype "input"))
      (node (ref "STM32F405") (pin "35") (pinfunction "PB14_35") (pintype "input"))
    )
    (net (code "72") (name "SPI2_MOSI") (class "Default")
      (node (ref "AT7456E") (pin "9") (pinfunction "SDIN_9") (pintype "input"))
      (node (ref "G21") (pin "1") (pinfunction "1_1") (pintype "input"))
      (node (ref "STM32F405") (pin "36") (pinfunction "PB15_36") (pintype "input"))
    )
    (net (code "73") (name "SPI3_CLK") (class "Default")
      (node (ref "G11") (pin "1") (pinfunction "1_1") (pintype "input"))
      (node (ref "STM32F405") (pin "55") (pinfunction "PB3_55") (pintype "input"))
      (node (ref "W25Q128") (pin "6") (pinfunction "CLK_6") (pintype "input"))
    )
    (net (code "74") (name "SPI3_MISO") (class "Default")
      (node (ref "G10") (pin "1") (pinfunction "1_1") (pintype "input"))
      (node (ref "STM32F405") (pin "56") (pinfunction "PB4_56") (pintype "input"))
      (node (ref "W25Q128") (pin "2") (pinfunction "DO/IO1_2") (pintype "input"))
    )
    (net (code "75") (name "SPI3_MOSI") (class "Default")
      (node (ref "G9") (pin "1") (pinfunction "1_1") (pintype "input"))
      (node (ref "STM32F405") (pin "57") (pinfunction "PB5_57") (pintype "input"))
      (node (ref "W25Q128") (pin "5") (pinfunction "DI/IO0_5") (pintype "input"))
    )
    (net (code "76") (name "SWCLK") (class "Default")
      (node (ref "STM32F405") (pin "49") (pinfunction "PA14_49") (pintype "input"))
      (node (ref "SWD") (pin "1") (pinfunction "1_1") (pintype "input"))
    )
    (net (code "77") (name "SWDIO{slash}OSD_CS") (class "Default")
      (node (ref "AT7456E") (pin "8") (pinfunction "CS#_8") (pintype "input"))
      (node (ref "G24") (pin "1") (pinfunction "1_1") (pintype "input"))
      (node (ref "R243") (pin "1") (pinfunction "1_1") (pintype "input"))
      (node (ref "STM32F405") (pin "46") (pinfunction "PA13_46") (pintype "input"))
      (node (ref "SWD") (pin "2") (pinfunction "2_2") (pintype "input"))
    )
    (net (code "78") (name "UART4_RX") (class "Default")
      (node (ref "DJI") (pin "4") (pinfunction "4_4") (pintype "input"))
      (node (ref "G3") (pin "1") (pinfunction "1_1") (pintype "input"))
      (node (ref "STM32F405") (pin "15") (pinfunction "PA1_15") (pintype "input"))
    )
    (net (code "79") (name "UART4_TX") (class "Default")
      (node (ref "DJI") (pin "3") (pinfunction "3_3") (pintype "input"))
      (node (ref "G2") (pin "1") (pinfunction "1_1") (pintype "input"))
      (node (ref "STM32F405") (pin "14") (pinfunction "PA0-WKUP_14") (pintype "input"))
    )
    (net (code "80") (name "UART5_RX") (class "Default")
      (node (ref "G25") (pin "1") (pinfunction "1_1") (pintype "input"))
      (node (ref "STM32F405") (pin "54") (pinfunction "PD2_54") (pintype "input"))
    )
    (net (code "81") (name "UART5_TX") (class "Default")
      (node (ref "G26") (pin "1") (pinfunction "1_1") (pintype "input"))
      (node (ref "STM32F405") (pin "53") (pinfunction "PC12_53") (pintype "input"))
    )
    (net (code "82") (name "USART1_RX") (class "Default")
      (node (ref "G8") (pin "1") (pinfunction "1_1") (pintype "input"))
      (node (ref "GPS") (pin "3") (pinfunction "3_3") (pintype "input"))
      (node (ref "STM32F405") (pin "43") (pinfunction "PA10_43") (pintype "input"))
    )
    (net (code "83") (name "USART1_TX") (class "Default")
      (node (ref "G7") (pin "1") (pinfunction "1_1") (pintype "input"))
      (node (ref "GPS") (pin "4") (pinfunction "4_4") (pintype "input"))
      (node (ref "STM32F405") (pin "42") (pinfunction "PA9_42") (pintype "input"))
    )
    (net (code "84") (name "USART2_RX") (class "Default")
      (node (ref "ELRS") (pin "1") (pinfunction "1_1") (pintype "input"))
      (node (ref "G13") (pin "1") (pinfunction "1_1") (pintype "input"))
      (node (ref "Q2") (pin "3") (pinfunction "3_3") (pintype "unspecified"))
      (node (ref "R26") (pin "1") (pinfunction "1_1") (pintype "input"))
      (node (ref "STM32F405") (pin "17") (pinfunction "PA3_17") (pintype "input"))
    )
    (net (code "85") (name "USART2_TX") (class "Default")
      (node (ref "ELRS") (pin "2") (pinfunction "2_2") (pintype "input"))
      (node (ref "G4") (pin "1") (pinfunction "1_1") (pintype "input"))
      (node (ref "STM32F405") (pin "16") (pinfunction "PA2_16") (pintype "input"))
    )
    (net (code "86") (name "USART3_RX") (class "Default")
      (node (ref "ESC") (pin "7") (pinfunction "7_7") (pintype "input"))
      (node (ref "STM32F405") (pin "52") (pinfunction "PC11_52") (pintype "input"))
    )
    (net (code "87") (name "USART3_TX") (class "Default")
      (node (ref "STM32F405") (pin "51") (pinfunction "PC10_51") (pintype "input"))
      (node (ref "VTX") (pin "2") (pinfunction "2_2") (pintype "input"))
    )
    (net (code "88") (name "USB_5V") (class "Default")
      (node (ref "D305") (pin "2") (pinfunction "A_2") (pintype "input"))
      (node (ref "USBC") (pin "A4") (pinfunction "VBUS_A4") (pintype "input"))
      (node (ref "USBC") (pin "A9") (pinfunction "VBUS_A9") (pintype "input"))
      (node (ref "USBC") (pin "B4") (pinfunction "VBUS_B4") (pintype "input"))
      (node (ref "USBC") (pin "B9") (pinfunction "VBUS_B9") (pintype "input"))
    )
    (net (code "89") (name "USB_DM") (class "Default")
      (node (ref "R17") (pin "1") (pinfunction "1_1") (pintype "input"))
      (node (ref "STM32F405") (pin "44") (pinfunction "PA11_44") (pintype "input"))
    )
    (net (code "90") (name "USB_DP") (class "Default")
      (node (ref "R18") (pin "1") (pinfunction "1_1") (pintype "input"))
      (node (ref "STM32F405") (pin "45") (pinfunction "PA12_45") (pintype "input"))
    )
    (net (code "91") (name "VBAT") (class "Default")
      (node (ref "C1A1") (pin "2") (pinfunction "2_2") (pintype "input"))
      (node (ref "C1A2") (pin "2") (pinfunction "2_2") (pintype "input"))
      (node (ref "C1B1") (pin "2") (pinfunction "2_2") (pintype "input"))
      (node (ref "C1B2") (pin "2") (pinfunction "2_2") (pintype "input"))
      (node (ref "C1C1") (pin "2") (pinfunction "2_2") (pintype "input"))
      (node (ref "C1C2") (pin "2") (pinfunction "2_2") (pintype "input"))
      (node (ref "D301") (pin "1") (pinfunction "1_1") (pintype "input"))
      (node (ref "ESC") (pin "2") (pinfunction "2_2") (pintype "input"))
      (node (ref "MP9943_5V") (pin "7") (pinfunction "IN_7") (pintype "input"))
      (node (ref "MP9943_9V") (pin "7") (pinfunction "IN_7") (pintype "input"))
      (node (ref "R22") (pin "2") (pinfunction "2_2") (pintype "input"))
      (node (ref "R234") (pin "2") (pinfunction "2_2") (pintype "input"))
      (node (ref "R240") (pin "2") (pinfunction "2_2") (pintype "input"))
    )
    (net (code "92") (name "VTX") (class "Default")
      (node (ref "R212") (pin "2") (pinfunction "2_2") (pintype "input"))
      (node (ref "VTX") (pin "1") (pinfunction "1_1") (pintype "input"))
    )
    (net (code "93") (name "unconnected-(AT7456E-CLKOUT-Pad7)") (class "Default")
      (node (ref "AT7456E") (pin "7") (pinfunction "CLKOUT_7") (pintype "input+no_connect"))
    )
    (net (code "94") (name "unconnected-(AT7456E-NC-Pad1)") (class "Default")
      (node (ref "AT7456E") (pin "1") (pinfunction "NC_1") (pintype "input+no_connect"))
    )
    (net (code "95") (name "unconnected-(AT7456E-NC-Pad2)") (class "Default")
      (node (ref "AT7456E") (pin "2") (pinfunction "NC_2") (pintype "input+no_connect"))
    )
    (net (code "96") (name "unconnected-(AT7456E-NC-Pad14)") (class "Default")
      (node (ref "AT7456E") (pin "14") (pinfunction "NC_14") (pintype "input+no_connect"))
    )
    (net (code "97") (name "unconnected-(AT7456E-NC-Pad15)") (class "Default")
      (node (ref "AT7456E") (pin "15") (pinfunction "NC_15") (pintype "input+no_connect"))
    )
    (net (code "98") (name "unconnected-(AT7456E-NC-Pad16)") (class "Default")
      (node (ref "AT7456E") (pin "16") (pinfunction "NC_16") (pintype "input+no_connect"))
    )
    (net (code "99") (name "unconnected-(AT7456E-NC-Pad27)") (class "Default")
      (node (ref "AT7456E") (pin "27") (pinfunction "NC_27") (pintype "input+no_connect"))
    )
    (net (code "100") (name "unconnected-(AT7456E-NC-Pad28)") (class "Default")
      (node (ref "AT7456E") (pin "28") (pinfunction "NC_28") (pintype "input+no_connect"))
    )
    (net (code "101") (name "unconnected-(AT7456E-SYNC_IN-Pad13)") (class "Default")
      (node (ref "AT7456E") (pin "13") (pinfunction "SYNC_IN_13") (pintype "input+no_connect"))
    )
    (net (code "102") (name "unconnected-(ICM-42688P-INT2{slash}FSYNC{slash}CLKIN-Pad9)") (class "Default")
      (node (ref "ICM-42688P") (pin "9") (pinfunction "INT2/FSYNC/CLKIN_9") (pintype "input+no_connect"))
    )
    (net (code "103") (name "unconnected-(ICM-42688P-RESV-Pad2)") (class "Default")
      (node (ref "ICM-42688P") (pin "2") (pinfunction "RESV_2") (pintype "input+no_connect"))
    )
    (net (code "104") (name "unconnected-(ICM-42688P-RESV-Pad3)") (class "Default")
      (node (ref "ICM-42688P") (pin "3") (pinfunction "RESV_3") (pintype "input+no_connect"))
    )
    (net (code "105") (name "unconnected-(ICM-42688P-RESV-Pad10)") (class "Default")
      (node (ref "ICM-42688P") (pin "10") (pinfunction "RESV_10") (pintype "input+no_connect"))
    )
    (net (code "106") (name "unconnected-(LDO-NC-Pad4)") (class "Default")
      (node (ref "LDO") (pin "4") (pinfunction "NC_4") (pintype "input+no_connect"))
    )
    (net (code "107") (name "unconnected-(LDO_GYRO-NC-Pad4)") (class "Default")
      (node (ref "LDO_GYRO") (pin "4") (pinfunction "NC_4") (pintype "input+no_connect"))
    )
    (net (code "108") (name "unconnected-(MPU6000-AUX_CL-Pad7)") (class "Default")
      (node (ref "MPU6000") (pin "7") (pinfunction "AUX_CL_7") (pintype "input+no_connect"))
    )
    (net (code "109") (name "unconnected-(MPU6000-AUX_DA-Pad6)") (class "Default")
      (node (ref "MPU6000") (pin "6") (pinfunction "AUX_DA_6") (pintype "input+no_connect"))
    )
    (net (code "110") (name "unconnected-(MPU6000-CLKOUT-Pad22)") (class "Default")
      (node (ref "MPU6000") (pin "22") (pinfunction "CLKOUT_22") (pintype "input+no_connect"))
    )
    (net (code "111") (name "unconnected-(MPU6000-FSYNC-Pad11)") (class "Default")
      (node (ref "MPU6000") (pin "11") (pinfunction "FSYNC_11") (pintype "input+no_connect"))
    )
    (net (code "112") (name "unconnected-(MPU6000-NC-Pad2)") (class "Default")
      (node (ref "MPU6000") (pin "2") (pinfunction "NC_2") (pintype "input+no_connect"))
    )
    (net (code "113") (name "unconnected-(MPU6000-NC-Pad3)") (class "Default")
      (node (ref "MPU6000") (pin "3") (pinfunction "NC_3") (pintype "input+no_connect"))
    )
    (net (code "114") (name "unconnected-(MPU6000-NC-Pad4)") (class "Default")
      (node (ref "MPU6000") (pin "4") (pinfunction "NC_4") (pintype "input+no_connect"))
    )
    (net (code "115") (name "unconnected-(MPU6000-NC-Pad5)") (class "Default")
      (node (ref "MPU6000") (pin "5") (pinfunction "NC_5") (pintype "input+no_connect"))
    )
    (net (code "116") (name "unconnected-(MPU6000-NC-Pad14)") (class "Default")
      (node (ref "MPU6000") (pin "14") (pinfunction "NC_14") (pintype "input+no_connect"))
    )
    (net (code "117") (name "unconnected-(MPU6000-NC-Pad15)") (class "Default")
      (node (ref "MPU6000") (pin "15") (pinfunction "NC_15") (pintype "input+no_connect"))
    )
    (net (code "118") (name "unconnected-(MPU6000-NC-Pad16)") (class "Default")
      (node (ref "MPU6000") (pin "16") (pinfunction "NC_16") (pintype "input+no_connect"))
    )
    (net (code "119") (name "unconnected-(MPU6000-NC-Pad17)") (class "Default")
      (node (ref "MPU6000") (pin "17") (pinfunction "NC_17") (pintype "input+no_connect"))
    )
    (net (code "120") (name "unconnected-(MPU6000-RESV-Pad19)") (class "Default")
      (node (ref "MPU6000") (pin "19") (pinfunction "RESV_19") (pintype "input+no_connect"))
    )
    (net (code "121") (name "unconnected-(MPU6000-RESV-Pad21)") (class "Default")
      (node (ref "MPU6000") (pin "21") (pinfunction "RESV_21") (pintype "input+no_connect"))
    )
    (net (code "122") (name "unconnected-(STM32F405-PA8-Pad41)") (class "Default")
      (node (ref "STM32F405") (pin "41") (pinfunction "PA8_41") (pintype "input+no_connect"))
    )
    (net (code "123") (name "unconnected-(STM32F405-PA15-Pad50)") (class "Default")
      (node (ref "STM32F405") (pin "50") (pinfunction "PA15_50") (pintype "input+no_connect"))
    )
    (net (code "124") (name "unconnected-(STM32F405-PB0-Pad26)") (class "Default")
      (node (ref "STM32F405") (pin "26") (pinfunction "PB0_26") (pintype "input+no_connect"))
    )
    (net (code "125") (name "unconnected-(STM32F405-PB9-Pad62)") (class "Default")
      (node (ref "STM32F405") (pin "62") (pinfunction "PB9_62") (pintype "input+no_connect"))
    )
    (net (code "126") (name "unconnected-(STM32F405-PB10-Pad29)") (class "Default")
      (node (ref "STM32F405") (pin "29") (pinfunction "PB10_29") (pintype "input+no_connect"))
    )
    (net (code "127") (name "unconnected-(STM32F405-PB11-Pad30)") (class "Default")
      (node (ref "STM32F405") (pin "30") (pinfunction "PB11_30") (pintype "input+no_connect"))
    )
    (net (code "128") (name "unconnected-(STM32F405-PB12-Pad33)") (class "Default")
      (node (ref "STM32F405") (pin "33") (pinfunction "PB12_33") (pintype "input+no_connect"))
    )
    (net (code "129") (name "unconnected-(STM32F405-PC3-Pad11)") (class "Default")
      (node (ref "STM32F405") (pin "11") (pinfunction "PC3_11") (pintype "input+no_connect"))
    )
    (net (code "130") (name "unconnected-(STM32F405-PC5-Pad25)") (class "Default")
      (node (ref "STM32F405") (pin "25") (pinfunction "PC5_25") (pintype "input+no_connect"))
    )
    (net (code "131") (name "unconnected-(STM32F405-PC15-Pad4)") (class "Default")
      (node (ref "STM32F405") (pin "4") (pinfunction "PC15_4") (pintype "input+no_connect"))
    )
    (net (code "132") (name "unconnected-(USBC-CC1-PadA5)") (class "Default")
      (node (ref "USBC") (pin "A5") (pinfunction "CC1_A5") (pintype "input+no_connect"))
    )
    (net (code "133") (name "unconnected-(USBC-CC2-PadB5)") (class "Default")
      (node (ref "USBC") (pin "B5") (pinfunction "CC2_B5") (pintype "input+no_connect"))
    )
    (net (code "134") (name "unconnected-(USBC-SUB1-PadA8)") (class "Default")
      (node (ref "USBC") (pin "A8") (pinfunction "SUB1_A8") (pintype "input+no_connect"))
    )
    (net (code "135") (name "unconnected-(USBC-SUB2-PadB8)") (class "Default")
      (node (ref "USBC") (pin "B8") (pinfunction "SUB2_B8") (pintype "input+no_connect"))
    )
  )
)
